# Zero_V1_0.net
KiCad netlist of a schematic drawn in EAGLE
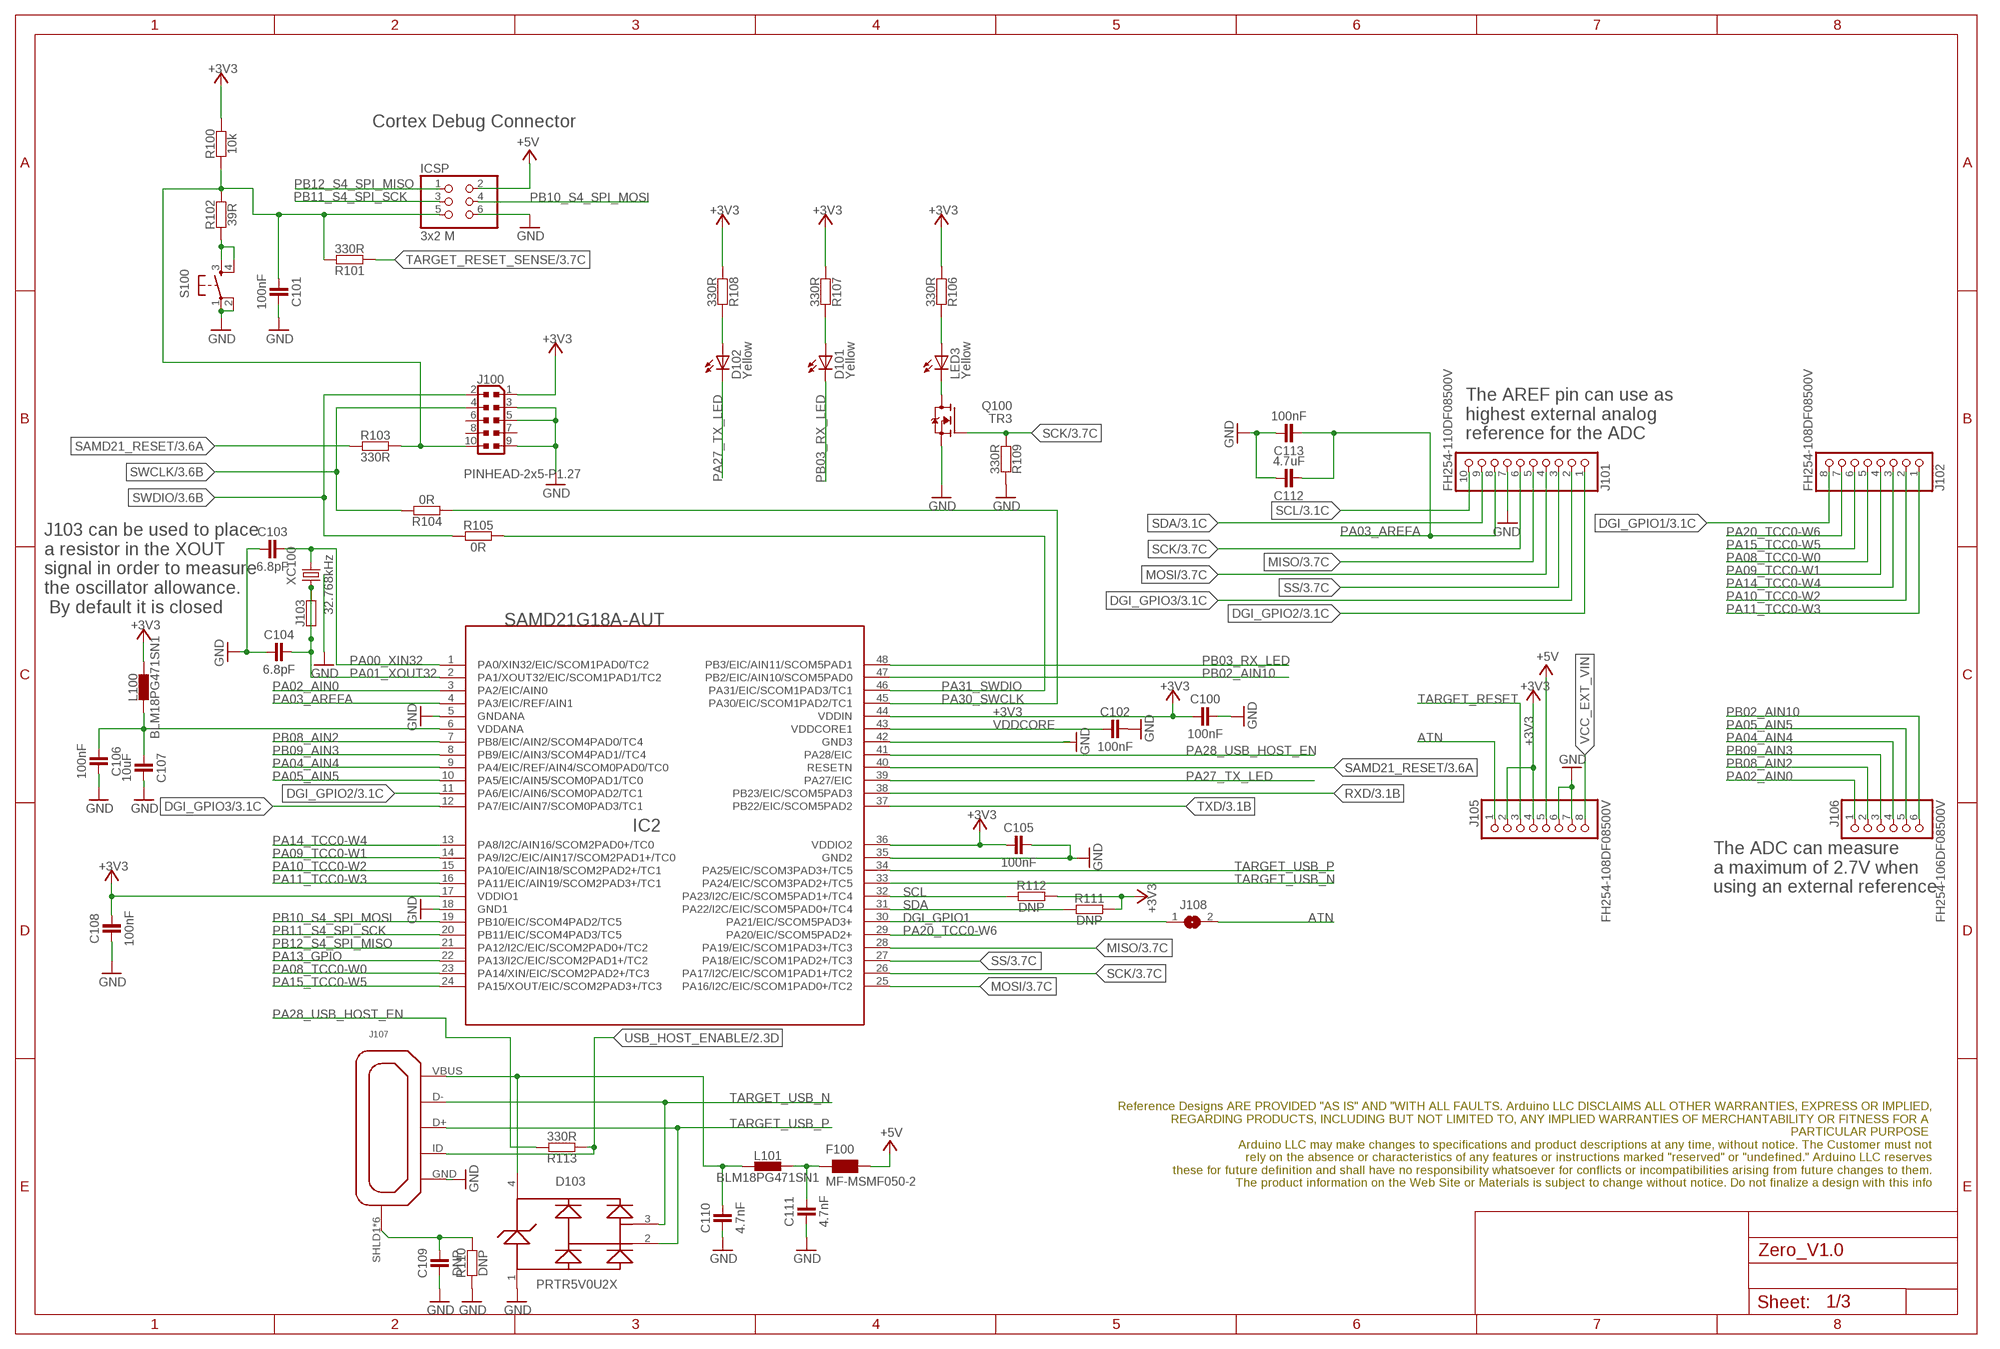
[diagram p0: schematic, sheet 1]
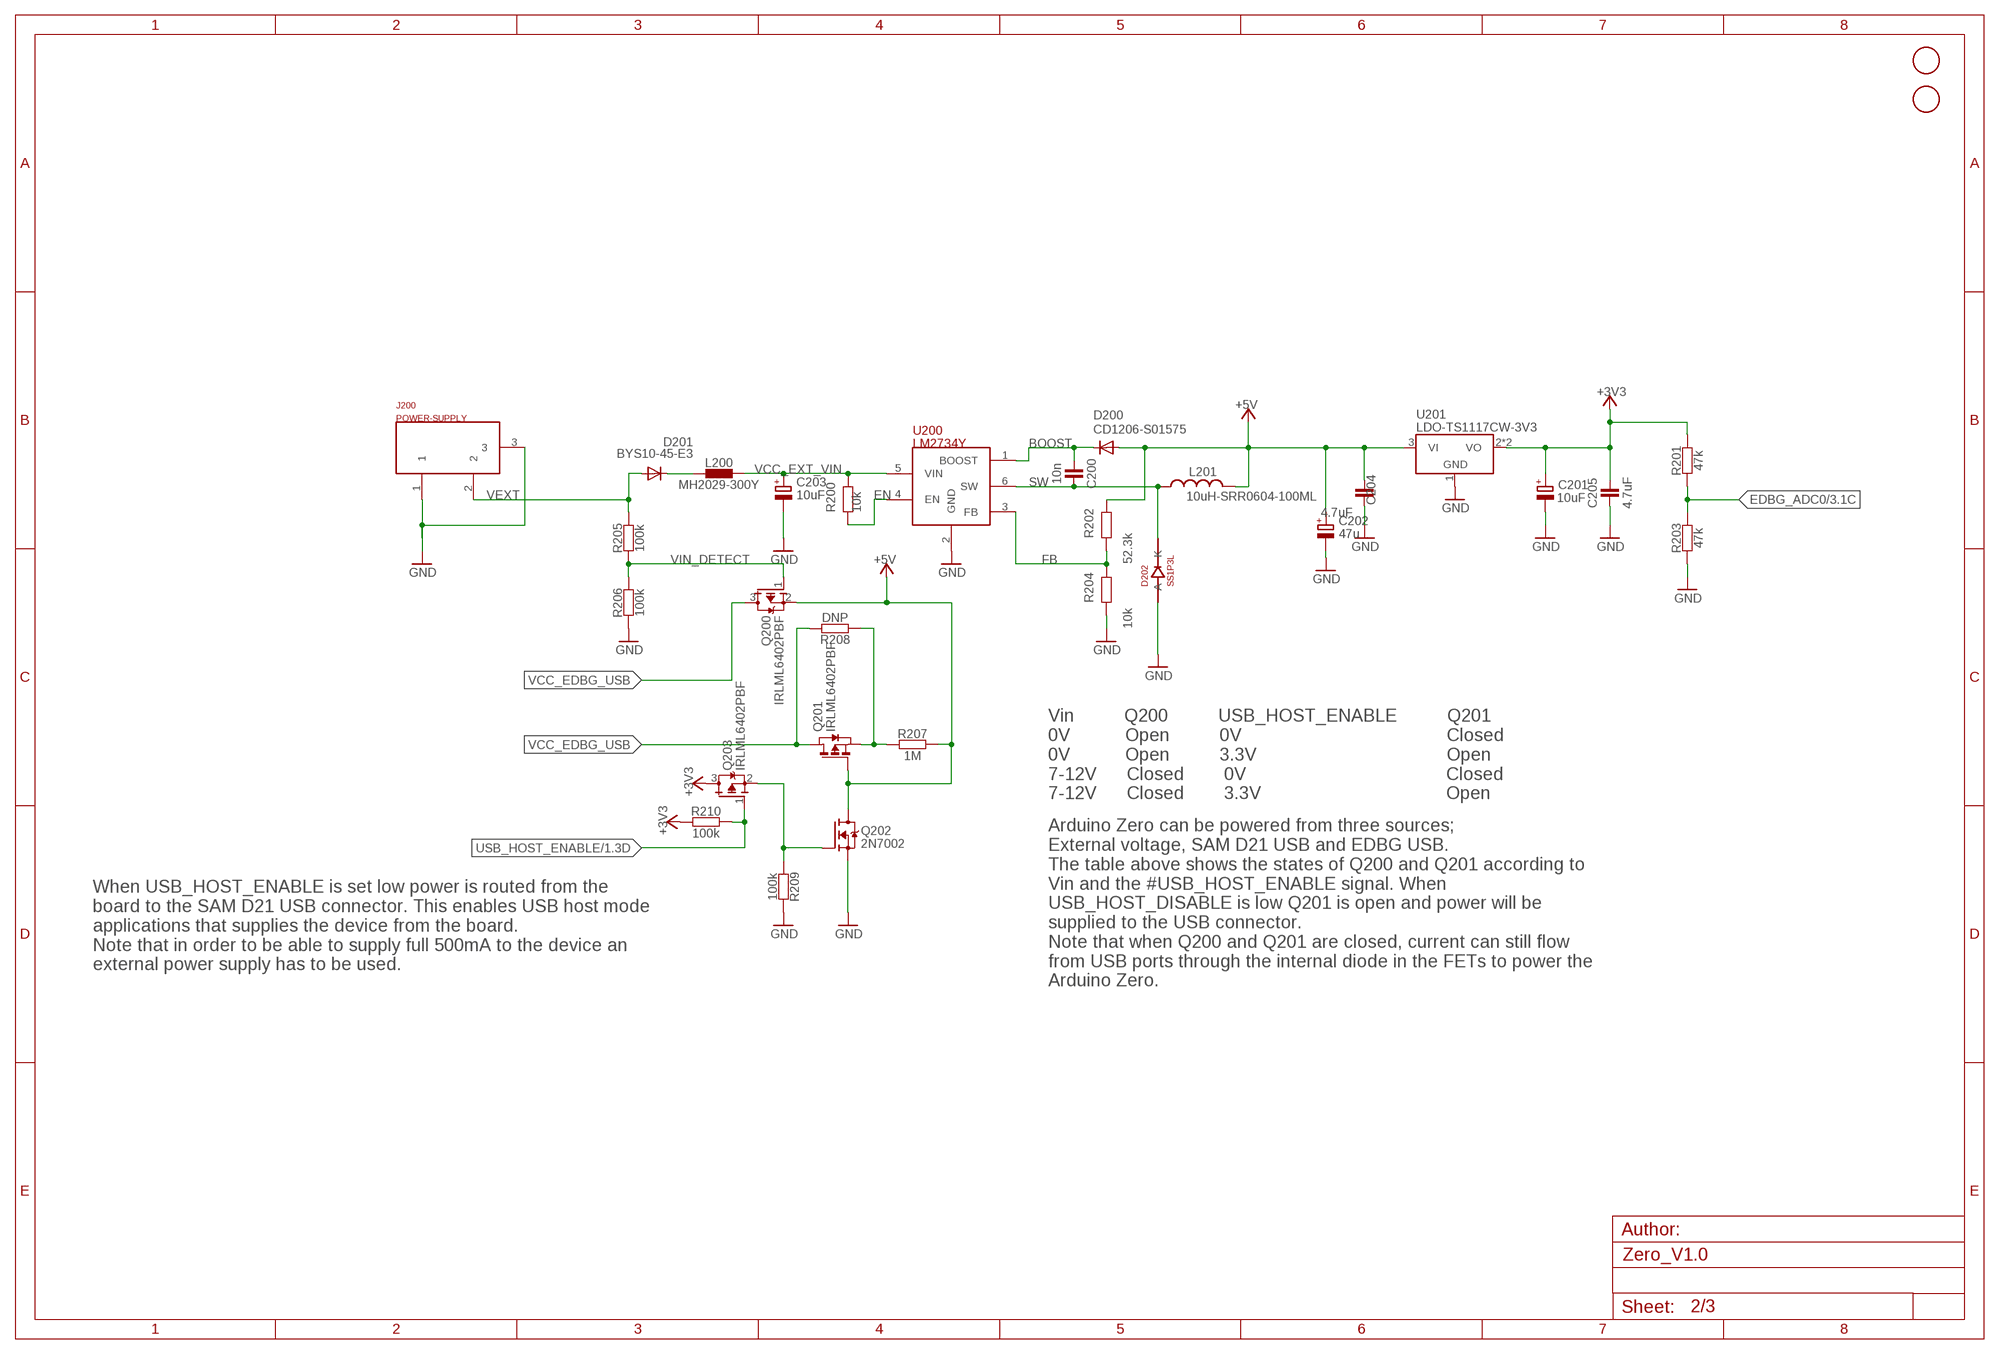
[diagram p1: schematic, sheet 2]
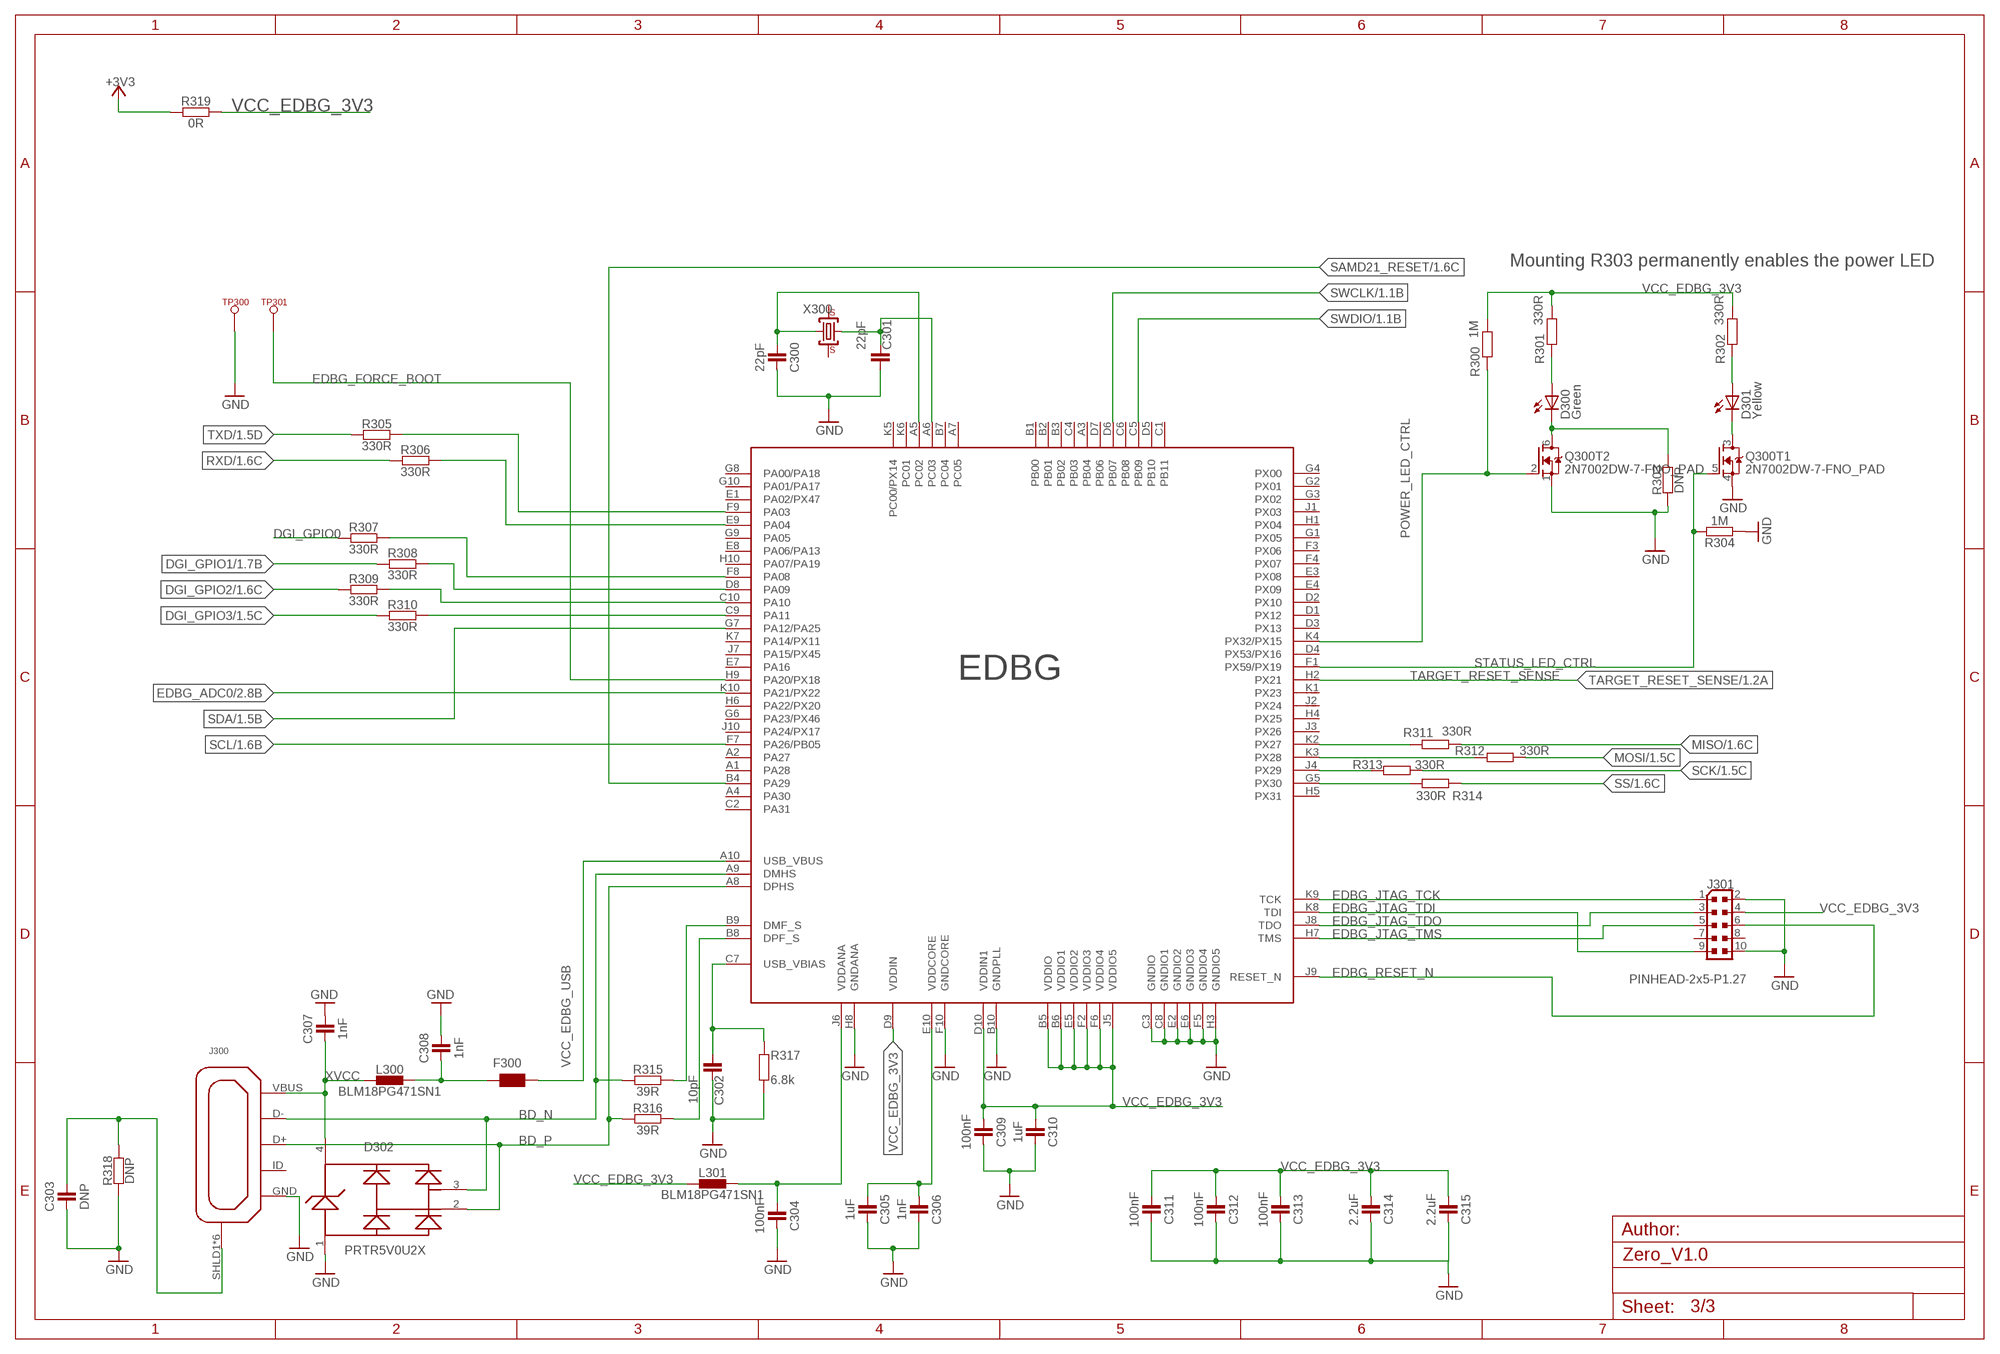
[diagram p2: schematic, sheet 3]

(export (version "E")
  (design (tool "Eeschema 10.0.6"))
  (components
    (comp (ref "C200")
      (value "10n")
      (footprint "eagle-import:C0402")
      (libsource (lib "eagle-import") (part "CAPACITORS-0402"))
    )
    (comp (ref "C201")
      (value "10uF")
      (footprint "eagle-import:PANASONIC_D")
      (fields (field (name "PART_NUMBER") "47uF"))
      (libsource (lib "eagle-import") (part "0113_47UF"))
    )
    (comp (ref "C202")
      (value "47u")
      (footprint "eagle-import:PANASONIC_D")
      (fields (field (name "PART_NUMBER") "47uF"))
      (libsource (lib "eagle-import") (part "0113_47UF"))
    )
    (comp (ref "C203")
      (value "10uF")
      (footprint "eagle-import:PANASONIC_D")
      (fields (field (name "PART_NUMBER") "47uF"))
      (libsource (lib "eagle-import") (part "0113_47UF"))
    )
    (comp (ref "C204")
      (value "4.7uF")
      (footprint "eagle-import:C0603")
      (libsource (lib "eagle-import") (part "CAPACITORS-0603"))
    )
    (comp (ref "C205")
      (value "4.7uF")
      (footprint "eagle-import:C0603")
      (libsource (lib "eagle-import") (part "CAPACITORS-0603"))
    )
    (comp (ref "D200")
      (value "CD1206-S01575")
      (footprint "eagle-import:MINIMELF")
      (libsource (lib "eagle-import") (part "0012_CD1206-S01575"))
    )
    (comp (ref "D201")
      (value "BYS10-45-E3")
      (footprint "eagle-import:MINIMELF")
      (fields (field (name "PART_NUMBER") "CD1206-S01575"))
      (libsource (lib "eagle-import") (part "0012_CD1206-S01575"))
    )
    (comp (ref "D202")
      (value "SS1P3L")
      (footprint "eagle-import:DO220AAL")
      (fields (field (name "PART_NUMBER") "SS1P3L-M3/84A"))
      (libsource (lib "eagle-import") (part "0025_SS1P3L-M3/84A"))
    )
    (comp (ref "FD1")
      (value "FIDUCIALMOUNT")
      (footprint "eagle-import:FIDUCIA-MOUNT")
      (libsource (lib "eagle-import") (part "FIDUCIALMOUNT"))
    )
    (comp (ref "FD2")
      (value "FIDUCIALMOUNT")
      (footprint "eagle-import:FIDUCIA-MOUNT")
      (libsource (lib "eagle-import") (part "FIDUCIALMOUNT"))
    )
    (comp (ref "J200")
      (value "POWER-SUPPLY")
      (footprint "eagle-import:POWERSUPPLY_DC-21MM")
      (fields (field (name "PART_NUMBER") "19746"))
      (libsource (lib "eagle-import") (part "0018_19746-POWER-SUPPLY"))
    )
    (comp (ref "L200")
      (value "MH2029-300Y")
      (footprint "eagle-import:C0805")
      (libsource (lib "eagle-import") (part "INDUCTOR-0805"))
    )
    (comp (ref "L201")
      (value "10uH-SRR0604-100ML")
      (footprint "eagle-import:SRR0604")
      (fields (field (name "PART_NUMBER") "SRR0604-100ML"))
      (libsource (lib "eagle-import") (part "0031_SRR0604-100ML"))
    )
    (comp (ref "Q200")
      (value "IRLML6402PBF")
      (footprint "eagle-import:SOT323")
      (libsource (lib "eagle-import") (part "IRLML6402PBF"))
    )
    (comp (ref "Q201")
      (value "IRLML6402PBF")
      (footprint "eagle-import:SOT-23")
      (fields (field (name "PART_NUMBER") "PMV48XP"))
      (libsource (lib "eagle-import") (part "0297_PMV48XP"))
    )
    (comp (ref "Q202")
      (value "2N7002")
      (footprint "eagle-import:SOT23")
      (libsource (lib "eagle-import") (part "MOSFET-N-SOT23"))
    )
    (comp (ref "Q203")
      (value "IRLML6402PBF")
      (footprint "eagle-import:SOT323")
      (libsource (lib "eagle-import") (part "IRLML6402PBF"))
    )
    (comp (ref "R200")
      (value "10k")
      (footprint "eagle-import:C0402")
      (libsource (lib "eagle-import") (part "RESISTORS-0402"))
    )
    (comp (ref "R201")
      (value "47k")
      (footprint "eagle-import:C0402")
      (libsource (lib "eagle-import") (part "RESISTORS-0402"))
    )
    (comp (ref "R202")
      (value "52.3k")
      (footprint "eagle-import:C0402")
      (libsource (lib "eagle-import") (part "RESISTORS-0402"))
    )
    (comp (ref "R203")
      (value "47k")
      (footprint "eagle-import:C0402")
      (libsource (lib "eagle-import") (part "RESISTORS-0402"))
    )
    (comp (ref "R204")
      (value "10k")
      (footprint "eagle-import:C0402")
      (libsource (lib "eagle-import") (part "RESISTORS-0402"))
    )
    (comp (ref "R205")
      (value "100k")
      (footprint "eagle-import:C0402")
      (libsource (lib "eagle-import") (part "RESISTORS-0402"))
    )
    (comp (ref "R206")
      (value "100k")
      (footprint "eagle-import:C0402")
      (libsource (lib "eagle-import") (part "RESISTORS-0402"))
    )
    (comp (ref "R207")
      (value "1M")
      (footprint "eagle-import:C0402")
      (libsource (lib "eagle-import") (part "RESISTORS-0402"))
    )
    (comp (ref "R208")
      (value "DNP")
      (footprint "eagle-import:C0402")
      (libsource (lib "eagle-import") (part "RESISTORS-0402"))
    )
    (comp (ref "R209")
      (value "100k")
      (footprint "eagle-import:C0402")
      (libsource (lib "eagle-import") (part "RESISTORS-0402"))
    )
    (comp (ref "R210")
      (value "100k")
      (footprint "eagle-import:C0402")
      (libsource (lib "eagle-import") (part "RESISTORS-0402"))
    )
    (comp (ref "U200")
      (value "LM2734Y")
      (footprint "eagle-import:SOT23-6")
      (fields (field (name "PART_NUMBER") "LM2734YMK"))
      (libsource (lib "eagle-import") (part "0179_LM2734YMK"))
    )
    (comp (ref "U201")
      (value "LDO-TS1117CW-3V3")
      (footprint "eagle-import:SOT223")
      (libsource (lib "eagle-import") (part "LDO-TS1117CW-3V3"))
    )
    (comp (ref "C300")
      (value "22pF")
      (footprint "eagle-import:C0402")
      (libsource (lib "eagle-import") (part "CAPACITORS-0402"))
    )
    (comp (ref "C301")
      (value "22pF")
      (footprint "eagle-import:C0402")
      (libsource (lib "eagle-import") (part "CAPACITORS-0402"))
    )
    (comp (ref "C302")
      (value "10pF")
      (footprint "eagle-import:C0402")
      (libsource (lib "eagle-import") (part "CAPACITORS-0402"))
    )
    (comp (ref "C303")
      (value "DNP")
      (footprint "eagle-import:C0402")
      (libsource (lib "eagle-import") (part "CAPACITORS-0402"))
    )
    (comp (ref "C304")
      (value "100nF")
      (footprint "eagle-import:C0402")
      (libsource (lib "eagle-import") (part "CAPACITORS-0402"))
    )
    (comp (ref "C305")
      (value "1uF")
      (footprint "eagle-import:C0402")
      (libsource (lib "eagle-import") (part "CAPACITORS-0402"))
    )
    (comp (ref "C306")
      (value "1nF")
      (footprint "eagle-import:C0402")
      (libsource (lib "eagle-import") (part "CAPACITORS-0402"))
    )
    (comp (ref "C307")
      (value "1nF")
      (footprint "eagle-import:C0402")
      (libsource (lib "eagle-import") (part "CAPACITORS-0402"))
    )
    (comp (ref "C308")
      (value "1nF")
      (footprint "eagle-import:C0402")
      (libsource (lib "eagle-import") (part "CAPACITORS-0402"))
    )
    (comp (ref "C309")
      (value "100nF")
      (footprint "eagle-import:C0402")
      (libsource (lib "eagle-import") (part "CAPACITORS-0402"))
    )
    (comp (ref "C310")
      (value "1uF")
      (footprint "eagle-import:C0402")
      (libsource (lib "eagle-import") (part "CAPACITORS-0402"))
    )
    (comp (ref "C311")
      (value "100nF")
      (footprint "eagle-import:C0402")
      (libsource (lib "eagle-import") (part "CAPACITORS-0402"))
    )
    (comp (ref "C312")
      (value "100nF")
      (footprint "eagle-import:C0402")
      (libsource (lib "eagle-import") (part "CAPACITORS-0402"))
    )
    (comp (ref "C313")
      (value "100nF")
      (footprint "eagle-import:C0402")
      (libsource (lib "eagle-import") (part "CAPACITORS-0402"))
    )
    (comp (ref "C314")
      (value "2.2uF")
      (footprint "eagle-import:C0402")
      (libsource (lib "eagle-import") (part "CAPACITORS-0402"))
    )
    (comp (ref "C315")
      (value "2.2uF")
      (footprint "eagle-import:C0402")
      (libsource (lib "eagle-import") (part "CAPACITORS-0402"))
    )
    (comp (ref "D300")
      (value "Green")
      (footprint "eagle-import:CHIPLED_0805")
      (fields (field (name "PART_NUMBER") "KPT-2012SGC"))
      (libsource (lib "eagle-import") (part "0043_KPT-2012SGC"))
    )
    (comp (ref "D301")
      (value "Yellow")
      (footprint "eagle-import:CHIPLED_0805")
      (fields (field (name "PART_NUMBER") "KPT-2012SGC"))
      (libsource (lib "eagle-import") (part "0043_KPT-2012SGC"))
    )
    (comp (ref "D302")
      (value "PRTR5V0U2XB")
      (footprint "eagle-import:SOT143B")
      (libsource (lib "eagle-import") (part "PRTR5V0U2XB"))
    )
    (comp (ref "EDBG")
      (value "EDBG")
      (footprint "eagle-import:VFBGA100")
      (libsource (lib "eagle-import") (part "EDBG"))
    )
    (comp (ref "F300")
      (value "WUERTH-ELEKTRONIK_WE-CBF_1812")
      (footprint "eagle-import:WUERTH-ELEKTRONIK_1812")
      (libsource (lib "eagle-import") (part "WUERTH-ELEKTRONIK_WE-CBF_1812"))
    )
    (comp (ref "J300")
      (value "ZX62-AB-5PA")
      (footprint "eagle-import:USB-MICRO-10103594")
      (libsource (lib "eagle-import") (part "ZX62-AB-5PA"))
    )
    (comp (ref "J301")
      (value "PINHEAD-2x5-P1.27")
      (footprint "eagle-import:PINHEAD_2X05_127")
      (libsource (lib "eagle-import") (part "0171_PH127-205DF055G00AROUND-PADS"))
    )
    (comp (ref "L300")
      (value "BLM18PG471SN1")
      (footprint "eagle-import:C0603")
      (libsource (lib "eagle-import") (part "INDUCTOR-0603"))
    )
    (comp (ref "L301")
      (value "BLM18PG471SN1")
      (footprint "eagle-import:C0603")
      (libsource (lib "eagle-import") (part "INDUCTOR-0603"))
    )
    (comp (ref "Q300")
      (value "2N7002DW-7-FNO_PAD")
      (footprint "eagle-import:PWR_SC70-6L2")
      (libsource (lib "eagle-import") (part "2N7002DW-7-FNO_PAD"))
    )
    (comp (ref "R300")
      (value "1M")
      (footprint "eagle-import:C0402")
      (libsource (lib "eagle-import") (part "RESISTORS-0402"))
    )
    (comp (ref "R301")
      (value "330R")
      (footprint "eagle-import:C0402")
      (libsource (lib "eagle-import") (part "RESISTORS-0402"))
    )
    (comp (ref "R302")
      (value "330R")
      (footprint "eagle-import:C0402")
      (libsource (lib "eagle-import") (part "RESISTORS-0402"))
    )
    (comp (ref "R303")
      (value "DNP")
      (footprint "eagle-import:C0402")
      (libsource (lib "eagle-import") (part "RESISTORS-0402"))
    )
    (comp (ref "R304")
      (value "1M")
      (footprint "eagle-import:C0402")
      (libsource (lib "eagle-import") (part "RESISTORS-0402"))
    )
    (comp (ref "R305")
      (value "330R")
      (footprint "eagle-import:C0402")
      (libsource (lib "eagle-import") (part "RESISTORS-0402"))
    )
    (comp (ref "R306")
      (value "330R")
      (footprint "eagle-import:C0402")
      (libsource (lib "eagle-import") (part "RESISTORS-0402"))
    )
    (comp (ref "R307")
      (value "330R")
      (footprint "eagle-import:C0402")
      (libsource (lib "eagle-import") (part "RESISTORS-0402"))
    )
    (comp (ref "R308")
      (value "330R")
      (footprint "eagle-import:C0402")
      (libsource (lib "eagle-import") (part "RESISTORS-0402"))
    )
    (comp (ref "R309")
      (value "330R")
      (footprint "eagle-import:C0402")
      (libsource (lib "eagle-import") (part "RESISTORS-0402"))
    )
    (comp (ref "R310")
      (value "330R")
      (footprint "eagle-import:C0402")
      (libsource (lib "eagle-import") (part "RESISTORS-0402"))
    )
    (comp (ref "R311")
      (value "330R")
      (footprint "eagle-import:C0402")
      (libsource (lib "eagle-import") (part "RESISTORS-0402"))
    )
    (comp (ref "R312")
      (value "330R")
      (footprint "eagle-import:C0402")
      (libsource (lib "eagle-import") (part "RESISTORS-0402"))
    )
    (comp (ref "R313")
      (value "330R")
      (footprint "eagle-import:C0402")
      (libsource (lib "eagle-import") (part "RESISTORS-0402"))
    )
    (comp (ref "R314")
      (value "330R")
      (footprint "eagle-import:C0402")
      (libsource (lib "eagle-import") (part "RESISTORS-0402"))
    )
    (comp (ref "R315")
      (value "39R")
      (footprint "eagle-import:C0402")
      (libsource (lib "eagle-import") (part "RESISTORS-0402"))
    )
    (comp (ref "R316")
      (value "39R")
      (footprint "eagle-import:C0402")
      (libsource (lib "eagle-import") (part "RESISTORS-0402"))
    )
    (comp (ref "R317")
      (value "6.8k")
      (footprint "eagle-import:C0402")
      (libsource (lib "eagle-import") (part "RESISTORS-0402"))
    )
    (comp (ref "R318")
      (value "DNP")
      (footprint "eagle-import:C0402")
      (libsource (lib "eagle-import") (part "RESISTORS-0402"))
    )
    (comp (ref "R319")
      (value "0R")
      (footprint "eagle-import:C0402")
      (libsource (lib "eagle-import") (part "RESISTORS-0402"))
    )
    (comp (ref "TP300")
      (value "TP_SP")
      (footprint "eagle-import:TP-SP")
      (libsource (lib "eagle-import") (part "TP_SP"))
    )
    (comp (ref "TP301")
      (value "TP_SP")
      (footprint "eagle-import:TP-SP")
      (libsource (lib "eagle-import") (part "TP_SP"))
    )
    (comp (ref "X300")
      (value "12mHz-12pF-K7")
      (footprint "eagle-import:CRYSTAL-5.4-3.2")
      (libsource (lib "eagle-import") (part "12MHZ-12PF-K75.4-3.2"))
    )
    (comp (ref "C100")
      (value "100nF")
      (footprint "eagle-import:C0402")
      (libsource (lib "eagle-import") (part "CAPACITORS-0402"))
    )
    (comp (ref "C101")
      (value "100nF")
      (footprint "eagle-import:C0402")
      (libsource (lib "eagle-import") (part "CAPACITORS-0402"))
    )
    (comp (ref "C102")
      (value "100nF")
      (footprint "eagle-import:C0402")
      (libsource (lib "eagle-import") (part "CAPACITORS-0402"))
    )
    (comp (ref "C103")
      (value "6.8pF")
      (footprint "eagle-import:C0402")
      (libsource (lib "eagle-import") (part "CAPACITORS-0402"))
    )
    (comp (ref "C104")
      (value "6.8pF")
      (footprint "eagle-import:C0402")
      (libsource (lib "eagle-import") (part "CAPACITORS-0402"))
    )
    (comp (ref "C105")
      (value "100nF")
      (footprint "eagle-import:C0402")
      (libsource (lib "eagle-import") (part "CAPACITORS-0402"))
    )
    (comp (ref "C106")
      (value "100nF")
      (footprint "eagle-import:C0402")
      (libsource (lib "eagle-import") (part "CAPACITORS-0402"))
    )
    (comp (ref "C107")
      (value "10uF")
      (footprint "eagle-import:C0603")
      (libsource (lib "eagle-import") (part "CAPACITORS-0603"))
    )
    (comp (ref "C108")
      (value "100nF")
      (footprint "eagle-import:C0402")
      (libsource (lib "eagle-import") (part "CAPACITORS-0402"))
    )
    (comp (ref "C109")
      (value "DNP")
      (footprint "eagle-import:C0402")
      (libsource (lib "eagle-import") (part "CAPACITORS-0402"))
    )
    (comp (ref "C110")
      (value "4.7nF")
      (footprint "eagle-import:C0402")
      (libsource (lib "eagle-import") (part "CAPACITORS-0402"))
    )
    (comp (ref "C111")
      (value "4.7nF")
      (footprint "eagle-import:C0402")
      (libsource (lib "eagle-import") (part "CAPACITORS-0402"))
    )
    (comp (ref "C112")
      (value "4.7uF")
      (footprint "eagle-import:C0603")
      (libsource (lib "eagle-import") (part "CAPACITORS-0603"))
    )
    (comp (ref "C113")
      (value "100nF")
      (footprint "eagle-import:C0402")
      (libsource (lib "eagle-import") (part "CAPACITORS-0402"))
    )
    (comp (ref "D101")
      (value "Yellow")
      (footprint "eagle-import:CHIPLED_0805")
      (fields (field (name "PART_NUMBER") "KPT-2012YC"))
      (libsource (lib "eagle-import") (part "0044_KPT-2012YC"))
    )
    (comp (ref "D102")
      (value "Yellow")
      (footprint "eagle-import:CHIPLED_0805")
      (fields (field (name "PART_NUMBER") "KPT-2012YC"))
      (libsource (lib "eagle-import") (part "0044_KPT-2012YC"))
    )
    (comp (ref "D103")
      (value "PRTR5V0U2XB")
      (footprint "eagle-import:SOT143B")
      (libsource (lib "eagle-import") (part "PRTR5V0U2XB"))
    )
    (comp (ref "F100")
      (value "MF-MSMF050-2")
      (footprint "eagle-import:WUERTH-ELEKTRONIK_1812")
      (libsource (lib "eagle-import") (part "WUERTH-ELEKTRONIK_WE-CBF_1812"))
    )
    (comp (ref "IC2")
      (value "SAMD21G18A-AUT")
      (footprint "eagle-import:TQFP48")
      (libsource (lib "eagle-import") (part "SAMD21G18A"))
    )
    (comp (ref "ICSP")
      (value "3x2 M")
      (footprint "eagle-import:2X03")
      (libsource (lib "eagle-import") (part "ICSP"))
    )
    (comp (ref "J100")
      (value "PINHEAD-2x5-P1.27")
      (footprint "eagle-import:PINHEAD_2X05_127")
      (libsource (lib "eagle-import") (part "0171_PH127-205DF055G00AROUND-PADS"))
    )
    (comp (ref "J101")
      (value "FH254-110DF08500V")
      (footprint "eagle-import:1X10")
      (fields (field (name "PART_NUMBER") "20TW-537"))
      (libsource (lib "eagle-import") (part "1684_20TW-537"))
    )
    (comp (ref "J102")
      (value "FH254-108DF08500V")
      (footprint "eagle-import:1X08")
      (fields (field (name "PART_NUMBER") "20TW-536"))
      (libsource (lib "eagle-import") (part "1683_20TW-536"))
    )
    (comp (ref "J103")
      (value "RESISTORS-0402")
      (footprint "eagle-import:C0402")
      (libsource (lib "eagle-import") (part "RESISTORS-0402"))
    )
    (comp (ref "J105")
      (value "FH254-108DF08500V")
      (footprint "eagle-import:1X08")
      (fields (field (name "PART_NUMBER") "20TW-536"))
      (libsource (lib "eagle-import") (part "1683_20TW-536"))
    )
    (comp (ref "J106")
      (value "FH254-106DF08500V")
      (footprint "eagle-import:1X06")
      (fields (field (name "PART_NUMBER") "20TW-535"))
      (libsource (lib "eagle-import") (part "1682_20TW-535_STD"))
    )
    (comp (ref "J107")
      (value "ZX62-AB-5PA")
      (footprint "eagle-import:USB-MICRO-10103594")
      (libsource (lib "eagle-import") (part "ZX62-AB-5PA"))
    )
    (comp (ref "J108")
      (value "SJ")
      (footprint "eagle-import:SJ")
      (libsource (lib "eagle-import") (part "SJ"))
    )
    (comp (ref "L100")
      (value "BLM18PG471SN1")
      (footprint "eagle-import:C0603")
      (libsource (lib "eagle-import") (part "INDUCTOR-0603"))
    )
    (comp (ref "L101")
      (value "BLM18PG471SN1")
      (footprint "eagle-import:C0603")
      (libsource (lib "eagle-import") (part "INDUCTOR-0603"))
    )
    (comp (ref "LED3")
      (value "Yellow")
      (footprint "eagle-import:CHIPLED_0805")
      (fields (field (name "PART_NUMBER") "KPT-2012YC"))
      (libsource (lib "eagle-import") (part "0044_KPT-2012YC"))
    )
    (comp (ref "R100")
      (value "10k")
      (footprint "eagle-import:C0402")
      (libsource (lib "eagle-import") (part "RESISTORS-0402"))
    )
    (comp (ref "R101")
      (value "330R")
      (footprint "eagle-import:C0402")
      (libsource (lib "eagle-import") (part "RESISTORS-0402"))
    )
    (comp (ref "R102")
      (value "39R")
      (footprint "eagle-import:C0402")
      (libsource (lib "eagle-import") (part "RESISTORS-0402"))
    )
    (comp (ref "R103")
      (value "330R")
      (footprint "eagle-import:C0402")
      (libsource (lib "eagle-import") (part "RESISTORS-0402"))
    )
    (comp (ref "R104")
      (value "0R")
      (footprint "eagle-import:C0402")
      (libsource (lib "eagle-import") (part "RESISTORS-0402"))
    )
    (comp (ref "R105")
      (value "0R")
      (footprint "eagle-import:C0402")
      (libsource (lib "eagle-import") (part "RESISTORS-0402"))
    )
    (comp (ref "R106")
      (value "330R")
      (footprint "eagle-import:C0402")
      (libsource (lib "eagle-import") (part "RESISTORS-0402"))
    )
    (comp (ref "R107")
      (value "330R")
      (footprint "eagle-import:C0402")
      (libsource (lib "eagle-import") (part "RESISTORS-0402"))
    )
    (comp (ref "R108")
      (value "330R")
      (footprint "eagle-import:C0402")
      (libsource (lib "eagle-import") (part "RESISTORS-0402"))
    )
    (comp (ref "R109")
      (value "330R")
      (footprint "eagle-import:C0402")
      (libsource (lib "eagle-import") (part "RESISTORS-0402"))
    )
    (comp (ref "R110")
      (value "DNP")
      (footprint "eagle-import:C0402")
      (libsource (lib "eagle-import") (part "RESISTORS-0402"))
    )
    (comp (ref "R111")
      (value "DNP")
      (footprint "eagle-import:C0402")
      (libsource (lib "eagle-import") (part "RESISTORS-0402"))
    )
    (comp (ref "R112")
      (value "DNP")
      (footprint "eagle-import:C0402")
      (libsource (lib "eagle-import") (part "RESISTORS-0402"))
    )
    (comp (ref "R113")
      (value "330R")
      (footprint "eagle-import:C0402")
      (libsource (lib "eagle-import") (part "RESISTORS-0402"))
    )
    (comp (ref "S100")
      (value "PUSHBUTTON3")
      (footprint "eagle-import:TS42_4PINS")
      (libsource (lib "eagle-import") (part "PUSHBUTTON3"))
    )
    (comp (ref "TR3")
      (value "Q100")
      (footprint "eagle-import:SOT-23")
      (libsource (lib "eagle-import") (part "1612_2N7002LT1G"))
    )
    (comp (ref "U$5")
      (value "DNP")
      (footprint "eagle-import:FRAME")
      (libsource (lib "eagle-import") (part "A3-FRAME-STANDARD"))
    )
    (comp (ref "XC100")
      (value "32.768kHz")
      (footprint "eagle-import:CRYSTAL_TC26SMD")
      (libsource (lib "eagle-import") (part "CRYSTALSMD"))
    )
  )
  (nets
    (net (code "1") (name "+3V3") (class "Default")
      (node (ref "C100") (pin "1") (pinfunction "1_1") (pintype "passive"))
      (node (ref "C105") (pin "1") (pinfunction "1_1") (pintype "passive"))
      (node (ref "C108") (pin "2") (pinfunction "2_2") (pintype "passive"))
      (node (ref "C201") (pin "+") (pinfunction "+_+") (pintype "passive"))
      (node (ref "C205") (pin "2") (pinfunction "2_2") (pintype "passive"))
      (node (ref "IC2") (pin "17") (pinfunction "VDDIO1_17") (pintype "power_in"))
      (node (ref "IC2") (pin "36") (pinfunction "VDDIO2_36") (pintype "power_in"))
      (node (ref "IC2") (pin "44") (pinfunction "VDDIN_44") (pintype "power_in"))
      (node (ref "J100") (pin "1") (pinfunction "1_1") (pintype "passive"))
      (node (ref "J105") (pin "2") (pinfunction "2_2") (pintype "passive"))
      (node (ref "J105") (pin "4") (pinfunction "4_4") (pintype "passive"))
      (node (ref "L100") (pin "2") (pinfunction "2_2") (pintype "passive"))
      (node (ref "Q203") (pin "3") (pinfunction "D_3") (pintype "passive"))
      (node (ref "R100") (pin "2") (pinfunction "2_2") (pintype "passive"))
      (node (ref "R106") (pin "1") (pinfunction "1_1") (pintype "passive"))
      (node (ref "R107") (pin "1") (pinfunction "1_1") (pintype "passive"))
      (node (ref "R108") (pin "1") (pinfunction "1_1") (pintype "passive"))
      (node (ref "R111") (pin "2") (pinfunction "2_2") (pintype "passive"))
      (node (ref "R112") (pin "2") (pinfunction "2_2") (pintype "passive"))
      (node (ref "R201") (pin "2") (pinfunction "2_2") (pintype "passive"))
      (node (ref "R210") (pin "1") (pinfunction "1_1") (pintype "passive"))
      (node (ref "R319") (pin "1") (pinfunction "1_1") (pintype "passive"))
      (node (ref "U201") (pin "2") (pinfunction "VO_2") (pintype "passive"))
      (node (ref "U201") (pin "4") (pinfunction "VO_4") (pintype "passive"))
    )
    (net (code "2") (name "+5V") (class "Default")
      (node (ref "C202") (pin "+") (pinfunction "+_+") (pintype "passive"))
      (node (ref "C204") (pin "1") (pinfunction "1_1") (pintype "passive"))
      (node (ref "D200") (pin "A") (pinfunction "A_A") (pintype "passive"))
      (node (ref "F100") (pin "2") (pinfunction "2_2") (pintype "passive"))
      (node (ref "ICSP") (pin "2") (pinfunction "2_2") (pintype "passive"))
      (node (ref "J105") (pin "5") (pinfunction "5_5") (pintype "passive"))
      (node (ref "L201") (pin "P$2") (pinfunction "2_P$2") (pintype "passive"))
      (node (ref "Q200") (pin "2") (pinfunction "S_2") (pintype "passive"))
      (node (ref "Q201") (pin "3") (pinfunction "G_3") (pintype "passive"))
      (node (ref "Q202") (pin "3") (pinfunction "D_3") (pintype "passive"))
      (node (ref "R202") (pin "1") (pinfunction "1_1") (pintype "passive"))
      (node (ref "R207") (pin "2") (pinfunction "2_2") (pintype "passive"))
      (node (ref "U201") (pin "3") (pinfunction "VI_3") (pintype "input"))
    )
    (net (code "3") (name "ATN") (class "Default")
      (node (ref "J105") (pin "1") (pinfunction "1_1") (pintype "passive"))
      (node (ref "J108") (pin "2") (pinfunction "2_2") (pintype "passive"))
    )
    (net (code "4") (name "BD_N") (class "Default")
      (node (ref "D302") (pin "3") (pinfunction "3_3") (pintype "bidirectional"))
      (node (ref "EDBG") (pin "A9") (pinfunction "DMHS_A9") (pintype "bidirectional"))
      (node (ref "J300") (pin "D-") (pinfunction "D-_D-") (pintype "bidirectional"))
      (node (ref "R315") (pin "1") (pinfunction "1_1") (pintype "passive"))
    )
    (net (code "5") (name "BD_P") (class "Default")
      (node (ref "D302") (pin "2") (pinfunction "2_2") (pintype "bidirectional"))
      (node (ref "EDBG") (pin "A8") (pinfunction "DPHS_A8") (pintype "bidirectional"))
      (node (ref "J300") (pin "D+") (pinfunction "D+_D+") (pintype "bidirectional"))
      (node (ref "R316") (pin "1") (pinfunction "1_1") (pintype "passive"))
    )
    (net (code "6") (name "BOOST") (class "Default")
      (node (ref "C200") (pin "1") (pinfunction "1_1") (pintype "passive"))
      (node (ref "D200") (pin "C") (pinfunction "C_C") (pintype "passive"))
      (node (ref "U200") (pin "1") (pinfunction "BOOST_1") (pintype "input"))
    )
    (net (code "7") (name "DGI_GPIO0") (class "Default")
      (node (ref "R307") (pin "1") (pinfunction "1_1") (pintype "passive"))
    )
    (net (code "8") (name "DGI_GPIO1") (class "Default")
      (node (ref "IC2") (pin "30") (pinfunction "PA21/EIC/SCOM5PAD3+_30") (pintype "bidirectional"))
      (node (ref "J102") (pin "8") (pinfunction "8_8") (pintype "passive"))
      (node (ref "J108") (pin "1") (pinfunction "1_1") (pintype "passive"))
      (node (ref "R308") (pin "1") (pinfunction "1_1") (pintype "passive"))
    )
    (net (code "9") (name "DGI_GPIO2") (class "Default")
      (node (ref "IC2") (pin "11") (pinfunction "PA6/EIC/AIN6/SCOM0PAD2/TC1_11") (pintype "bidirectional"))
      (node (ref "J101") (pin "1") (pinfunction "1_1") (pintype "passive"))
      (node (ref "R309") (pin "1") (pinfunction "1_1") (pintype "passive"))
    )
    (net (code "10") (name "DGI_GPIO3") (class "Default")
      (node (ref "IC2") (pin "12") (pinfunction "PA7/EIC/AIN7/SCOM0PAD3/TC1_12") (pintype "bidirectional"))
      (node (ref "J101") (pin "2") (pinfunction "2_2") (pintype "passive"))
      (node (ref "R310") (pin "1") (pinfunction "1_1") (pintype "passive"))
    )
    (net (code "11") (name "EDBG_ADC0") (class "Default")
      (node (ref "EDBG") (pin "K10") (pinfunction "PA21/PX22_K10") (pintype "bidirectional"))
      (node (ref "R201") (pin "1") (pinfunction "1_1") (pintype "passive"))
      (node (ref "R203") (pin "2") (pinfunction "2_2") (pintype "passive"))
    )
    (net (code "12") (name "EDBG_FORCE_BOOT") (class "Default")
      (node (ref "EDBG") (pin "H9") (pinfunction "PA20/PX18_H9") (pintype "bidirectional"))
      (node (ref "TP301") (pin "X") (pinfunction "TESTP_X") (pintype "passive"))
    )
    (net (code "13") (name "EDBG_JTAG_TCK") (class "Default")
      (node (ref "EDBG") (pin "K9") (pinfunction "TCK_K9") (pintype "bidirectional"))
      (node (ref "J301") (pin "1") (pinfunction "1_1") (pintype "passive"))
    )
    (net (code "14") (name "EDBG_JTAG_TDI") (class "Default")
      (node (ref "EDBG") (pin "K8") (pinfunction "TDI_K8") (pintype "bidirectional"))
      (node (ref "J301") (pin "9") (pinfunction "9_9") (pintype "passive"))
    )
    (net (code "15") (name "EDBG_JTAG_TDO") (class "Default")
      (node (ref "EDBG") (pin "J8") (pinfunction "TDO_J8") (pintype "bidirectional"))
      (node (ref "J301") (pin "3") (pinfunction "3_3") (pintype "passive"))
    )
    (net (code "16") (name "EDBG_JTAG_TMS") (class "Default")
      (node (ref "EDBG") (pin "H7") (pinfunction "TMS_H7") (pintype "bidirectional"))
      (node (ref "J301") (pin "5") (pinfunction "5_5") (pintype "passive"))
    )
    (net (code "17") (name "EDBG_RESET_N") (class "Default")
      (node (ref "EDBG") (pin "J9") (pinfunction "RESET_N_J9") (pintype "bidirectional"))
      (node (ref "J301") (pin "6") (pinfunction "6_6") (pintype "passive"))
    )
    (net (code "18") (name "EN") (class "Default")
      (node (ref "R200") (pin "2") (pinfunction "2_2") (pintype "passive"))
      (node (ref "U200") (pin "4") (pinfunction "EN_4") (pintype "input"))
    )
    (net (code "19") (name "FB") (class "Default")
      (node (ref "R202") (pin "2") (pinfunction "2_2") (pintype "passive"))
      (node (ref "R204") (pin "1") (pinfunction "1_1") (pintype "passive"))
      (node (ref "U200") (pin "3") (pinfunction "FB_3") (pintype "input"))
    )
    (net (code "20") (name "GND") (class "Default")
      (node (ref "C100") (pin "2") (pinfunction "2_2") (pintype "passive"))
      (node (ref "C101") (pin "2") (pinfunction "2_2") (pintype "passive"))
      (node (ref "C102") (pin "2") (pinfunction "2_2") (pintype "passive"))
      (node (ref "C103") (pin "1") (pinfunction "1_1") (pintype "passive"))
      (node (ref "C104") (pin "1") (pinfunction "1_1") (pintype "passive"))
      (node (ref "C105") (pin "2") (pinfunction "2_2") (pintype "passive"))
      (node (ref "C106") (pin "2") (pinfunction "2_2") (pintype "passive"))
      (node (ref "C107") (pin "2") (pinfunction "2_2") (pintype "passive"))
      (node (ref "C108") (pin "1") (pinfunction "1_1") (pintype "passive"))
      (node (ref "C109") (pin "1") (pinfunction "1_1") (pintype "passive"))
      (node (ref "C110") (pin "1") (pinfunction "1_1") (pintype "passive"))
      (node (ref "C111") (pin "1") (pinfunction "1_1") (pintype "passive"))
      (node (ref "C112") (pin "2") (pinfunction "2_2") (pintype "passive"))
      (node (ref "C113") (pin "2") (pinfunction "2_2") (pintype "passive"))
      (node (ref "C201") (pin "-") (pinfunction "-_-") (pintype "passive"))
      (node (ref "C202") (pin "-") (pinfunction "-_-") (pintype "passive"))
      (node (ref "C203") (pin "-") (pinfunction "-_-") (pintype "passive"))
      (node (ref "C204") (pin "2") (pinfunction "2_2") (pintype "passive"))
      (node (ref "C205") (pin "1") (pinfunction "1_1") (pintype "passive"))
      (node (ref "C300") (pin "2") (pinfunction "2_2") (pintype "passive"))
      (node (ref "C301") (pin "2") (pinfunction "2_2") (pintype "passive"))
      (node (ref "C302") (pin "2") (pinfunction "2_2") (pintype "passive"))
      (node (ref "C303") (pin "1") (pinfunction "1_1") (pintype "passive"))
      (node (ref "C304") (pin "2") (pinfunction "2_2") (pintype "passive"))
      (node (ref "C305") (pin "2") (pinfunction "2_2") (pintype "passive"))
      (node (ref "C306") (pin "2") (pinfunction "2_2") (pintype "passive"))
      (node (ref "C307") (pin "2") (pinfunction "2_2") (pintype "passive"))
      (node (ref "C308") (pin "2") (pinfunction "2_2") (pintype "passive"))
      (node (ref "C309") (pin "2") (pinfunction "2_2") (pintype "passive"))
      (node (ref "C310") (pin "2") (pinfunction "2_2") (pintype "passive"))
      (node (ref "C311") (pin "2") (pinfunction "2_2") (pintype "passive"))
      (node (ref "C312") (pin "2") (pinfunction "2_2") (pintype "passive"))
      (node (ref "C313") (pin "2") (pinfunction "2_2") (pintype "passive"))
      (node (ref "C314") (pin "2") (pinfunction "2_2") (pintype "passive"))
      (node (ref "C315") (pin "2") (pinfunction "2_2") (pintype "passive"))
      (node (ref "D103") (pin "1") (pinfunction "1_1") (pintype "bidirectional"))
      (node (ref "D202") (pin "P$2") (pinfunction "A_P$2") (pintype "bidirectional"))
      (node (ref "D302") (pin "1") (pinfunction "1_1") (pintype "bidirectional"))
      (node (ref "EDBG") (pin "B10") (pinfunction "GNDPLL_B10") (pintype "bidirectional"))
      (node (ref "EDBG") (pin "C3") (pinfunction "GNDIO_C3") (pintype "bidirectional"))
      (node (ref "EDBG") (pin "C8") (pinfunction "GNDIO1_C8") (pintype "bidirectional"))
      (node (ref "EDBG") (pin "E2") (pinfunction "GNDIO2_E2") (pintype "bidirectional"))
      (node (ref "EDBG") (pin "E6") (pinfunction "GNDIO3_E6") (pintype "bidirectional"))
      (node (ref "EDBG") (pin "F10") (pinfunction "GNDCORE_F10") (pintype "bidirectional"))
      (node (ref "EDBG") (pin "F5") (pinfunction "GNDIO4_F5") (pintype "bidirectional"))
      (node (ref "EDBG") (pin "H3") (pinfunction "GNDIO5_H3") (pintype "bidirectional"))
      (node (ref "EDBG") (pin "H8") (pinfunction "GNDANA_H8") (pintype "bidirectional"))
      (node (ref "IC2") (pin "18") (pinfunction "GND1_18") (pintype "power_in"))
      (node (ref "IC2") (pin "35") (pinfunction "GND2_35") (pintype "power_in"))
      (node (ref "IC2") (pin "42") (pinfunction "GND3_42") (pintype "power_in"))
      (node (ref "IC2") (pin "5") (pinfunction "GNDANA_5") (pintype "power_in"))
      (node (ref "ICSP") (pin "6") (pinfunction "6_6") (pintype "passive"))
      (node (ref "J100") (pin "3") (pinfunction "3_3") (pintype "passive"))
      (node (ref "J100") (pin "5") (pinfunction "5_5") (pintype "passive"))
      (node (ref "J100") (pin "9") (pinfunction "9_9") (pintype "passive"))
      (node (ref "J101") (pin "7") (pinfunction "7_7") (pintype "passive"))
      (node (ref "J105") (pin "6") (pinfunction "6_6") (pintype "passive"))
      (node (ref "J105") (pin "7") (pinfunction "7_7") (pintype "passive"))
      (node (ref "J107") (pin "GND") (pinfunction "GND_GND") (pintype "bidirectional"))
      (node (ref "J200") (pin "1") (pinfunction "1_1") (pintype "power_in"))
      (node (ref "J200") (pin "3") (pinfunction "3_3") (pintype "power_in"))
      (node (ref "J300") (pin "GND") (pinfunction "GND_GND") (pintype "bidirectional"))
      (node (ref "J301") (pin "10") (pinfunction "10_10") (pintype "passive"))
      (node (ref "J301") (pin "2") (pinfunction "2_2") (pintype "passive"))
      (node (ref "Q202") (pin "2") (pinfunction "S_2") (pintype "passive"))
      (node (ref "Q300") (pin "1") (pinfunction "S_1") (pintype "passive"))
      (node (ref "Q300") (pin "4") (pinfunction "S_4") (pintype "passive"))
      (node (ref "R109") (pin "2") (pinfunction "2_2") (pintype "passive"))
      (node (ref "R110") (pin "1") (pinfunction "1_1") (pintype "passive"))
      (node (ref "R203") (pin "1") (pinfunction "1_1") (pintype "passive"))
      (node (ref "R204") (pin "2") (pinfunction "2_2") (pintype "passive"))
      (node (ref "R206") (pin "1") (pinfunction "1_1") (pintype "passive"))
      (node (ref "R209") (pin "2") (pinfunction "2_2") (pintype "passive"))
      (node (ref "R303") (pin "1") (pinfunction "1_1") (pintype "passive"))
      (node (ref "R304") (pin "1") (pinfunction "1_1") (pintype "passive"))
      (node (ref "R317") (pin "1") (pinfunction "1_1") (pintype "passive"))
      (node (ref "R318") (pin "1") (pinfunction "1_1") (pintype "passive"))
      (node (ref "S100") (pin "1") (pinfunction "1_1") (pintype "passive"))
      (node (ref "S100") (pin "2") (pinfunction "2_2") (pintype "passive"))
      (node (ref "TP300") (pin "X") (pinfunction "TESTP_X") (pintype "passive"))
      (node (ref "TR3") (pin "2") (pinfunction "S_2") (pintype "passive"))
      (node (ref "U200") (pin "2") (pinfunction "GND_2") (pintype "power_in"))
      (node (ref "U201") (pin "1") (pinfunction "GND_1") (pintype "passive"))
      (node (ref "XC100") (pin "P$1") (pinfunction "GND_P$1") (pintype "bidirectional"))
    )
    (net (code "21") (name "MISO") (class "Default")
      (node (ref "IC2") (pin "28") (pinfunction "PA19/EIC/SCOM1PAD3+/TC3_28") (pintype "bidirectional"))
      (node (ref "J101") (pin "5") (pinfunction "5_5") (pintype "passive"))
      (node (ref "R311") (pin "2") (pinfunction "2_2") (pintype "passive"))
    )
    (net (code "22") (name "MOSI") (class "Default")
      (node (ref "IC2") (pin "25") (pinfunction "PA16/I2C/EIC/SCOM1PAD0+/TC2_25") (pintype "bidirectional"))
      (node (ref "J101") (pin "4") (pinfunction "4_4") (pintype "passive"))
      (node (ref "R312") (pin "2") (pinfunction "2_2") (pintype "passive"))
    )
    (net (code "23") (name "Net-(C109-Pad2)") (class "Default")
      (node (ref "C109") (pin "2") (pinfunction "2_2") (pintype "passive"))
      (node (ref "J107") (pin "SHLD1") (pinfunction "SH_SHLD1") (pintype "bidirectional"))
      (node (ref "J107") (pin "SHLD2") (pinfunction "SH_SHLD2") (pintype "bidirectional"))
      (node (ref "J107") (pin "SHLD3") (pinfunction "SH_SHLD3") (pintype "bidirectional"))
      (node (ref "J107") (pin "SHLD4") (pinfunction "SH_SHLD4") (pintype "bidirectional"))
      (node (ref "J107") (pin "SHLD5") (pinfunction "SH_SHLD5") (pintype "bidirectional"))
      (node (ref "J107") (pin "SHLD6") (pinfunction "SH_SHLD6") (pintype "bidirectional"))
      (node (ref "R110") (pin "2") (pinfunction "2_2") (pintype "passive"))
    )
    (net (code "24") (name "Net-(C111-Pad2)") (class "Default")
      (node (ref "C111") (pin "2") (pinfunction "2_2") (pintype "passive"))
      (node (ref "F100") (pin "1") (pinfunction "1_1") (pintype "passive"))
      (node (ref "L101") (pin "2") (pinfunction "2_2") (pintype "passive"))
    )
    (net (code "25") (name "Net-(C303-Pad2)") (class "Default")
      (node (ref "C303") (pin "2") (pinfunction "2_2") (pintype "passive"))
      (node (ref "J300") (pin "SHLD1") (pinfunction "SH_SHLD1") (pintype "bidirectional"))
      (node (ref "J300") (pin "SHLD2") (pinfunction "SH_SHLD2") (pintype "bidirectional"))
      (node (ref "J300") (pin "SHLD3") (pinfunction "SH_SHLD3") (pintype "bidirectional"))
      (node (ref "J300") (pin "SHLD4") (pinfunction "SH_SHLD4") (pintype "bidirectional"))
      (node (ref "J300") (pin "SHLD5") (pinfunction "SH_SHLD5") (pintype "bidirectional"))
      (node (ref "J300") (pin "SHLD6") (pinfunction "SH_SHLD6") (pintype "bidirectional"))
      (node (ref "R318") (pin "2") (pinfunction "2_2") (pintype "passive"))
    )
    (net (code "26") (name "Net-(C308-Pad1)") (class "Default")
      (node (ref "C308") (pin "1") (pinfunction "1_1") (pintype "passive"))
      (node (ref "F300") (pin "1") (pinfunction "1_1") (pintype "passive"))
      (node (ref "L300") (pin "2") (pinfunction "2_2") (pintype "passive"))
    )
    (net (code "27") (name "Net-(D101-PadA)") (class "Default")
      (node (ref "D101") (pin "A") (pinfunction "A_A") (pintype "passive"))
      (node (ref "R107") (pin "2") (pinfunction "2_2") (pintype "passive"))
    )
    (net (code "28") (name "Net-(D102-PadA)") (class "Default")
      (node (ref "D102") (pin "A") (pinfunction "A_A") (pintype "passive"))
      (node (ref "R108") (pin "2") (pinfunction "2_2") (pintype "passive"))
    )
    (net (code "29") (name "Net-(D201-PadC)") (class "Default")
      (node (ref "D201") (pin "C") (pinfunction "C_C") (pintype "passive"))
      (node (ref "L200") (pin "1") (pinfunction "1_1") (pintype "passive"))
    )
    (net (code "30") (name "Net-(D300-PadA)") (class "Default")
      (node (ref "D300") (pin "A") (pinfunction "A_A") (pintype "passive"))
      (node (ref "R301") (pin "1") (pinfunction "1_1") (pintype "passive"))
    )
    (net (code "31") (name "Net-(D301-PadA)") (class "Default")
      (node (ref "D301") (pin "A") (pinfunction "A_A") (pintype "passive"))
      (node (ref "R302") (pin "1") (pinfunction "1_1") (pintype "passive"))
    )
    (net (code "32") (name "Net-(EDBG-DMF_S)") (class "Default")
      (node (ref "EDBG") (pin "B9") (pinfunction "DMF_S_B9") (pintype "bidirectional"))
      (node (ref "R315") (pin "2") (pinfunction "2_2") (pintype "passive"))
    )
    (net (code "33") (name "Net-(EDBG-DPF_S)") (class "Default")
      (node (ref "EDBG") (pin "B8") (pinfunction "DPF_S_B8") (pintype "bidirectional"))
      (node (ref "R316") (pin "2") (pinfunction "2_2") (pintype "passive"))
    )
    (net (code "34") (name "Net-(EDBG-PA03)") (class "Default")
      (node (ref "EDBG") (pin "F9") (pinfunction "PA03_F9") (pintype "bidirectional"))
      (node (ref "R305") (pin "2") (pinfunction "2_2") (pintype "passive"))
    )
    (net (code "35") (name "Net-(EDBG-PA04)") (class "Default")
      (node (ref "EDBG") (pin "E9") (pinfunction "PA04_E9") (pintype "bidirectional"))
      (node (ref "R306") (pin "2") (pinfunction "2_2") (pintype "passive"))
    )
    (net (code "36") (name "Net-(EDBG-PA08)") (class "Default")
      (node (ref "EDBG") (pin "F8") (pinfunction "PA08_F8") (pintype "bidirectional"))
      (node (ref "R307") (pin "2") (pinfunction "2_2") (pintype "passive"))
    )
    (net (code "37") (name "Net-(EDBG-PA09)") (class "Default")
      (node (ref "EDBG") (pin "D8") (pinfunction "PA09_D8") (pintype "bidirectional"))
      (node (ref "R308") (pin "2") (pinfunction "2_2") (pintype "passive"))
    )
    (net (code "38") (name "Net-(EDBG-PA10)") (class "Default")
      (node (ref "EDBG") (pin "C10") (pinfunction "PA10_C10") (pintype "bidirectional"))
      (node (ref "R309") (pin "2") (pinfunction "2_2") (pintype "passive"))
    )
    (net (code "39") (name "Net-(EDBG-PA11)") (class "Default")
      (node (ref "EDBG") (pin "C9") (pinfunction "PA11_C9") (pintype "bidirectional"))
      (node (ref "R310") (pin "2") (pinfunction "2_2") (pintype "passive"))
    )
    (net (code "40") (name "Net-(EDBG-PC02)") (class "Default")
      (node (ref "C300") (pin "1") (pinfunction "1_1") (pintype "passive"))
      (node (ref "EDBG") (pin "A5") (pinfunction "PC02_A5") (pintype "bidirectional"))
      (node (ref "X300") (pin "3") (pinfunction "C2_3") (pintype "passive"))
    )
    (net (code "41") (name "Net-(EDBG-PC03)") (class "Default")
      (node (ref "C301") (pin "1") (pinfunction "1_1") (pintype "passive"))
      (node (ref "EDBG") (pin "A6") (pinfunction "PC03_A6") (pintype "bidirectional"))
      (node (ref "X300") (pin "1") (pinfunction "C1_1") (pintype "passive"))
    )
    (net (code "42") (name "Net-(EDBG-PX27)") (class "Default")
      (node (ref "EDBG") (pin "K2") (pinfunction "PX27_K2") (pintype "bidirectional"))
      (node (ref "R311") (pin "1") (pinfunction "1_1") (pintype "passive"))
    )
    (net (code "43") (name "Net-(EDBG-PX28)") (class "Default")
      (node (ref "EDBG") (pin "K3") (pinfunction "PX28_K3") (pintype "bidirectional"))
      (node (ref "R312") (pin "1") (pinfunction "1_1") (pintype "passive"))
    )
    (net (code "44") (name "Net-(EDBG-PX29)") (class "Default")
      (node (ref "EDBG") (pin "J4") (pinfunction "PX29_J4") (pintype "bidirectional"))
      (node (ref "R313") (pin "1") (pinfunction "1_1") (pintype "passive"))
    )
    (net (code "45") (name "Net-(EDBG-PX30)") (class "Default")
      (node (ref "EDBG") (pin "G5") (pinfunction "PX30_G5") (pintype "bidirectional"))
      (node (ref "R314") (pin "1") (pinfunction "1_1") (pintype "passive"))
    )
    (net (code "46") (name "Net-(EDBG-USB_VBIAS)") (class "Default")
      (node (ref "C302") (pin "1") (pinfunction "1_1") (pintype "passive"))
      (node (ref "EDBG") (pin "C7") (pinfunction "USB_VBIAS_C7") (pintype "bidirectional"))
      (node (ref "R317") (pin "2") (pinfunction "2_2") (pintype "passive"))
    )
    (net (code "47") (name "Net-(EDBG-VDDANA)") (class "Default")
      (node (ref "C304") (pin "1") (pinfunction "1_1") (pintype "passive"))
      (node (ref "EDBG") (pin "J6") (pinfunction "VDDANA_J6") (pintype "bidirectional"))
      (node (ref "L301") (pin "2") (pinfunction "2_2") (pintype "passive"))
    )
    (net (code "48") (name "Net-(EDBG-VDDCORE)") (class "Default")
      (node (ref "C305") (pin "1") (pinfunction "1_1") (pintype "passive"))
      (node (ref "C306") (pin "1") (pinfunction "1_1") (pintype "passive"))
      (node (ref "EDBG") (pin "E10") (pinfunction "VDDCORE_E10") (pintype "bidirectional"))
    )
    (net (code "49") (name "Net-(IC2-VDDANA)") (class "Default")
      (node (ref "C106") (pin "1") (pinfunction "1_1") (pintype "passive"))
      (node (ref "C107") (pin "1") (pinfunction "1_1") (pintype "passive"))
      (node (ref "IC2") (pin "6") (pinfunction "VDDANA_6") (pintype "power_in"))
      (node (ref "L100") (pin "1") (pinfunction "1_1") (pintype "passive"))
    )
    (net (code "50") (name "Net-(J107-VUSB)") (class "Default")
      (node (ref "C110") (pin "2") (pinfunction "2_2") (pintype "passive"))
      (node (ref "D103") (pin "4") (pinfunction "4_4") (pintype "bidirectional"))
      (node (ref "J107") (pin "VBUS") (pinfunction "VUSB_VBUS") (pintype "bidirectional"))
      (node (ref "L101") (pin "1") (pinfunction "1_1") (pintype "passive"))
    )
    (net (code "51") (name "Net-(LED3-PadA)") (class "Default")
      (node (ref "LED3") (pin "A") (pinfunction "A_A") (pintype "passive"))
      (node (ref "R106") (pin "2") (pinfunction "2_2") (pintype "passive"))
    )
    (net (code "52") (name "Net-(Q201-S)") (class "Default")
      (node (ref "Q201") (pin "2") (pinfunction "S_2") (pintype "passive"))
      (node (ref "R207") (pin "1") (pinfunction "1_1") (pintype "passive"))
      (node (ref "R208") (pin "1") (pinfunction "1_1") (pintype "passive"))
    )
    (net (code "53") (name "Net-(Q202-G)") (class "Default")
      (node (ref "Q202") (pin "1") (pinfunction "G_1") (pintype "passive"))
      (node (ref "Q203") (pin "2") (pinfunction "S_2") (pintype "passive"))
      (node (ref "R209") (pin "1") (pinfunction "1_1") (pintype "passive"))
    )
    (net (code "54") (name "Net-(Q300A-D)") (class "Default")
      (node (ref "D301") (pin "C") (pinfunction "C_C") (pintype "passive"))
      (node (ref "Q300") (pin "3") (pinfunction "D_3") (pintype "passive"))
    )
    (net (code "55") (name "Net-(Q300B-D)") (class "Default")
      (node (ref "D300") (pin "C") (pinfunction "C_C") (pintype "passive"))
      (node (ref "Q300") (pin "6") (pinfunction "D_6") (pintype "passive"))
      (node (ref "R303") (pin "2") (pinfunction "2_2") (pintype "passive"))
    )
    (net (code "56") (name "Net-(R102-Pad1)") (class "Default")
      (node (ref "R102") (pin "1") (pinfunction "1_1") (pintype "passive"))
      (node (ref "S100") (pin "3") (pinfunction "3_3") (pintype "passive"))
      (node (ref "S100") (pin "4") (pinfunction "4_4") (pintype "passive"))
    )
    (net (code "57") (name "Net-(TR3-D)") (class "Default")
      (node (ref "LED3") (pin "C") (pinfunction "C_C") (pintype "passive"))
      (node (ref "TR3") (pin "1") (pinfunction "D_1") (pintype "passive"))
    )
    (net (code "58") (name "PA00_XIN32") (class "Default")
      (node (ref "C103") (pin "2") (pinfunction "2_2") (pintype "passive"))
      (node (ref "IC2") (pin "1") (pinfunction "PA0/XIN32/EIC/SCOM1PAD0/TC2_1") (pintype "bidirectional"))
      (node (ref "XC100") (pin "2") (pinfunction "2_2") (pintype "passive"))
    )
    (net (code "59") (name "PA01_XOUT32") (class "Default")
      (node (ref "C104") (pin "2") (pinfunction "2_2") (pintype "passive"))
      (node (ref "IC2") (pin "2") (pinfunction "PA1/XOUT32/EIC/SCOM1PAD1/TC2_2") (pintype "bidirectional"))
      (node (ref "J103") (pin "1") (pinfunction "1_1") (pintype "passive"))
      (node (ref "J103") (pin "2") (pinfunction "2_2") (pintype "passive"))
      (node (ref "XC100") (pin "1") (pinfunction "1_1") (pintype "passive"))
    )
    (net (code "60") (name "PA02_AIN0") (class "Default")
      (node (ref "IC2") (pin "3") (pinfunction "PA2/EIC/AIN0_3") (pintype "bidirectional"))
      (node (ref "J106") (pin "1") (pinfunction "1_1") (pintype "passive"))
    )
    (net (code "61") (name "PA03_AREFA") (class "Default")
      (node (ref "C112") (pin "1") (pinfunction "1_1") (pintype "passive"))
      (node (ref "C113") (pin "1") (pinfunction "1_1") (pintype "passive"))
      (node (ref "IC2") (pin "4") (pinfunction "PA3/EIC/REF/AIN1_4") (pintype "bidirectional"))
      (node (ref "J101") (pin "8") (pinfunction "8_8") (pintype "passive"))
    )
    (net (code "62") (name "PA04_AIN4") (class "Default")
      (node (ref "IC2") (pin "9") (pinfunction "PA4/EIC/REF/AIN4/SCOM0PAD0/TC0_9") (pintype "bidirectional"))
      (node (ref "J106") (pin "4") (pinfunction "4_4") (pintype "passive"))
    )
    (net (code "63") (name "PA05_AIN5") (class "Default")
      (node (ref "IC2") (pin "10") (pinfunction "PA5/EIC/AIN5/SCOM0PAD1/TC0_10") (pintype "bidirectional"))
      (node (ref "J106") (pin "5") (pinfunction "5_5") (pintype "passive"))
    )
    (net (code "64") (name "PA08_TCC0-W0") (class "Default")
      (node (ref "IC2") (pin "23") (pinfunction "PA14/XIN/EIC/SCOM2PAD2+/TC3_23") (pintype "bidirectional"))
      (node (ref "J102") (pin "5") (pinfunction "5_5") (pintype "passive"))
    )
    (net (code "65") (name "PA09_TCC0-W1") (class "Default")
      (node (ref "IC2") (pin "14") (pinfunction "PA9/I2C/EIC/AIN17/SCOM2PAD1+/TC0_14") (pintype "bidirectional"))
      (node (ref "J102") (pin "4") (pinfunction "4_4") (pintype "passive"))
    )
    (net (code "66") (name "PA10_TCC0-W2") (class "Default")
      (node (ref "IC2") (pin "15") (pinfunction "PA10/EIC/AIN18/SCOM2PAD2+/TC1_15") (pintype "bidirectional"))
      (node (ref "J102") (pin "2") (pinfunction "2_2") (pintype "passive"))
    )
    (net (code "67") (name "PA11_TCC0-W3") (class "Default")
      (node (ref "IC2") (pin "16") (pinfunction "PA11/EIC/AIN19/SCOM2PAD3+/TC1_16") (pintype "bidirectional"))
      (node (ref "J102") (pin "1") (pinfunction "1_1") (pintype "passive"))
    )
    (net (code "68") (name "PA13_GPIO") (class "Default")
      (node (ref "IC2") (pin "22") (pinfunction "PA13/I2C/EIC/SCOM2PAD1+/TC2_22") (pintype "bidirectional"))
    )
    (net (code "69") (name "PA14_TCC0-W4") (class "Default")
      (node (ref "IC2") (pin "13") (pinfunction "PA8/I2C/AIN16/SCOM2PAD0+/TC0_13") (pintype "bidirectional"))
      (node (ref "J102") (pin "3") (pinfunction "3_3") (pintype "passive"))
    )
    (net (code "70") (name "PA15_TCC0-W5") (class "Default")
      (node (ref "IC2") (pin "24") (pinfunction "PA15/XOUT/EIC/SCOM2PAD3+/TC3_24") (pintype "bidirectional"))
      (node (ref "J102") (pin "6") (pinfunction "6_6") (pintype "passive"))
    )
    (net (code "71") (name "PA20_TCC0-W6") (class "Default")
      (node (ref "IC2") (pin "29") (pinfunction "PA20/EIC/SCOM5PAD2+_29") (pintype "bidirectional"))
      (node (ref "J102") (pin "7") (pinfunction "7_7") (pintype "passive"))
    )
    (net (code "72") (name "PA27_TX_LED") (class "Default")
      (node (ref "D102") (pin "C") (pinfunction "C_C") (pintype "passive"))
      (node (ref "IC2") (pin "39") (pinfunction "PA27/EIC_39") (pintype "bidirectional"))
    )
    (net (code "73") (name "PA28_USB_HOST_EN") (class "Default")
      (node (ref "IC2") (pin "41") (pinfunction "PA28/EIC_41") (pintype "bidirectional"))
      (node (ref "R113") (pin "2") (pinfunction "2_2") (pintype "passive"))
    )
    (net (code "74") (name "PA30_SWCLK") (class "Default")
      (node (ref "IC2") (pin "45") (pinfunction "PA30/EIC/SCOM1PAD2/TC1_45") (pintype "bidirectional"))
      (node (ref "R104") (pin "1") (pinfunction "1_1") (pintype "passive"))
    )
    (net (code "75") (name "PA31_SWDIO") (class "Default")
      (node (ref "IC2") (pin "46") (pinfunction "PA31/EIC/SCOM1PAD3/TC1_46") (pintype "bidirectional"))
      (node (ref "R105") (pin "2") (pinfunction "2_2") (pintype "passive"))
    )
    (net (code "76") (name "PB02_AIN10") (class "Default")
      (node (ref "IC2") (pin "47") (pinfunction "PB2/EIC/AIN10/SCOM5PAD0_47") (pintype "bidirectional"))
      (node (ref "J106") (pin "6") (pinfunction "6_6") (pintype "passive"))
    )
    (net (code "77") (name "PB03_RX_LED") (class "Default")
      (node (ref "D101") (pin "C") (pinfunction "C_C") (pintype "passive"))
      (node (ref "IC2") (pin "48") (pinfunction "PB3/EIC/AIN11/SCOM5PAD1_48") (pintype "bidirectional"))
    )
    (net (code "78") (name "PB08_AIN2") (class "Default")
      (node (ref "IC2") (pin "7") (pinfunction "PB8/EIC/AIN2/SCOM4PAD0/TC4_7") (pintype "bidirectional"))
      (node (ref "J106") (pin "2") (pinfunction "2_2") (pintype "passive"))
    )
    (net (code "79") (name "PB09_AIN3") (class "Default")
      (node (ref "IC2") (pin "8") (pinfunction "PB9/EIC/AIN3/SCOM4PAD1//TC4_8") (pintype "bidirectional"))
      (node (ref "J106") (pin "3") (pinfunction "3_3") (pintype "passive"))
    )
    (net (code "80") (name "PB10_S4_SPI_MOSI") (class "Default")
      (node (ref "IC2") (pin "19") (pinfunction "PB10/EIC/SCOM4PAD2/TC5_19") (pintype "bidirectional"))
      (node (ref "ICSP") (pin "4") (pinfunction "4_4") (pintype "passive"))
    )
    (net (code "81") (name "PB11_S4_SPI_SCK") (class "Default")
      (node (ref "IC2") (pin "20") (pinfunction "PB11/EIC/SCOM4PAD3/TC5_20") (pintype "bidirectional"))
      (node (ref "ICSP") (pin "3") (pinfunction "3_3") (pintype "passive"))
    )
    (net (code "82") (name "PB12_S4_SPI_MISO") (class "Default")
      (node (ref "IC2") (pin "21") (pinfunction "PA12/I2C/EIC/SCOM2PAD0+/TC2_21") (pintype "bidirectional"))
      (node (ref "ICSP") (pin "1") (pinfunction "1_1") (pintype "passive"))
    )
    (net (code "83") (name "POWER_LED_CTRL") (class "Default")
      (node (ref "EDBG") (pin "K4") (pinfunction "PX32/PX15_K4") (pintype "bidirectional"))
      (node (ref "Q300") (pin "2") (pinfunction "G_2") (pintype "passive"))
      (node (ref "R300") (pin "1") (pinfunction "1_1") (pintype "passive"))
    )
    (net (code "84") (name "RXD") (class "Default")
      (node (ref "IC2") (pin "38") (pinfunction "PB23/EIC/SCOM5PAD3_38") (pintype "bidirectional"))
      (node (ref "R306") (pin "1") (pinfunction "1_1") (pintype "passive"))
    )
    (net (code "85") (name "SAMD21_RESET") (class "Default")
      (node (ref "EDBG") (pin "B4") (pinfunction "PA29_B4") (pintype "bidirectional"))
      (node (ref "IC2") (pin "40") (pinfunction "RESETN_40") (pintype "bidirectional"))
      (node (ref "R103") (pin "1") (pinfunction "1_1") (pintype "passive"))
    )
    (net (code "86") (name "SCK") (class "Default")
      (node (ref "IC2") (pin "26") (pinfunction "PA17/I2C/EIC/SCOM1PAD1+/TC2_26") (pintype "bidirectional"))
      (node (ref "J101") (pin "6") (pinfunction "6_6") (pintype "passive"))
      (node (ref "R109") (pin "1") (pinfunction "1_1") (pintype "passive"))
      (node (ref "R313") (pin "2") (pinfunction "2_2") (pintype "passive"))
      (node (ref "TR3") (pin "3") (pinfunction "G_3") (pintype "passive"))
    )
    (net (code "87") (name "SCL") (class "Default")
      (node (ref "EDBG") (pin "F7") (pinfunction "PA26/PB05_F7") (pintype "bidirectional"))
      (node (ref "IC2") (pin "32") (pinfunction "PA23/I2C/EIC/SCOM5PAD1+/TC4_32") (pintype "bidirectional"))
      (node (ref "J101") (pin "10") (pinfunction "10_10") (pintype "passive"))
      (node (ref "R112") (pin "1") (pinfunction "1_1") (pintype "passive"))
    )
    (net (code "88") (name "SDA") (class "Default")
      (node (ref "EDBG") (pin "G7") (pinfunction "PA12/PA25_G7") (pintype "bidirectional"))
      (node (ref "IC2") (pin "31") (pinfunction "PA22/I2C/EIC/SCOM5PAD0+/TC4_31") (pintype "bidirectional"))
      (node (ref "J101") (pin "9") (pinfunction "9_9") (pintype "passive"))
      (node (ref "R111") (pin "1") (pinfunction "1_1") (pintype "passive"))
    )
    (net (code "89") (name "SS") (class "Default")
      (node (ref "IC2") (pin "27") (pinfunction "PA18/EIC/SCOM1PAD2+/TC3_27") (pintype "bidirectional"))
      (node (ref "J101") (pin "3") (pinfunction "3_3") (pintype "passive"))
      (node (ref "R314") (pin "2") (pinfunction "2_2") (pintype "passive"))
    )
    (net (code "90") (name "STATUS_LED_CTRL") (class "Default")
      (node (ref "EDBG") (pin "F1") (pinfunction "PX59/PX19_F1") (pintype "bidirectional"))
      (node (ref "Q300") (pin "5") (pinfunction "G_5") (pintype "passive"))
      (node (ref "R304") (pin "2") (pinfunction "2_2") (pintype "passive"))
    )
    (net (code "91") (name "SW") (class "Default")
      (node (ref "C200") (pin "2") (pinfunction "2_2") (pintype "passive"))
      (node (ref "D202") (pin "P$1") (pinfunction "K_P$1") (pintype "bidirectional"))
      (node (ref "L201") (pin "P$1") (pinfunction "1_P$1") (pintype "passive"))
      (node (ref "U200") (pin "6") (pinfunction "SW_6") (pintype "output"))
    )
    (net (code "92") (name "SWCLK") (class "Default")
      (node (ref "EDBG") (pin "D6") (pinfunction "PB07_D6") (pintype "bidirectional"))
      (node (ref "J100") (pin "4") (pinfunction "4_4") (pintype "passive"))
      (node (ref "R104") (pin "2") (pinfunction "2_2") (pintype "passive"))
    )
    (net (code "93") (name "SWDIO") (class "Default")
      (node (ref "EDBG") (pin "C5") (pinfunction "PB09_C5") (pintype "bidirectional"))
      (node (ref "J100") (pin "2") (pinfunction "2_2") (pintype "passive"))
      (node (ref "R105") (pin "1") (pinfunction "1_1") (pintype "passive"))
    )
    (net (code "94") (name "TARGET_RESET") (class "Default")
      (node (ref "C101") (pin "1") (pinfunction "1_1") (pintype "passive"))
      (node (ref "ICSP") (pin "5") (pinfunction "5_5") (pintype "passive"))
      (node (ref "J100") (pin "10") (pinfunction "10_10") (pintype "passive"))
      (node (ref "J105") (pin "3") (pinfunction "3_3") (pintype "passive"))
      (node (ref "R100") (pin "1") (pinfunction "1_1") (pintype "passive"))
      (node (ref "R101") (pin "2") (pinfunction "2_2") (pintype "passive"))
      (node (ref "R102") (pin "2") (pinfunction "2_2") (pintype "passive"))
      (node (ref "R103") (pin "2") (pinfunction "2_2") (pintype "passive"))
    )
    (net (code "95") (name "TARGET_RESET_SENSE") (class "Default")
      (node (ref "EDBG") (pin "H2") (pinfunction "PX21_H2") (pintype "bidirectional"))
      (node (ref "R101") (pin "1") (pinfunction "1_1") (pintype "passive"))
    )
    (net (code "96") (name "TARGET_USB_N") (class "Default")
      (node (ref "D103") (pin "3") (pinfunction "3_3") (pintype "bidirectional"))
      (node (ref "IC2") (pin "33") (pinfunction "PA24/EIC/SCOM3PAD2+/TC5_33") (pintype "bidirectional"))
      (node (ref "J107") (pin "D-") (pinfunction "D-_D-") (pintype "bidirectional"))
    )
    (net (code "97") (name "TARGET_USB_P") (class "Default")
      (node (ref "D103") (pin "2") (pinfunction "2_2") (pintype "bidirectional"))
      (node (ref "IC2") (pin "34") (pinfunction "PA25/EIC/SCOM3PAD3+/TC5_34") (pintype "bidirectional"))
      (node (ref "J107") (pin "D+") (pinfunction "D+_D+") (pintype "bidirectional"))
    )
    (net (code "98") (name "TXD") (class "Default")
      (node (ref "IC2") (pin "37") (pinfunction "PB22/EIC/SCOM5PAD2_37") (pintype "bidirectional"))
      (node (ref "R305") (pin "1") (pinfunction "1_1") (pintype "passive"))
    )
    (net (code "99") (name "USB_HOST_ENABLE") (class "Default")
      (node (ref "J107") (pin "ID") (pinfunction "ID_ID") (pintype "bidirectional"))
      (node (ref "Q203") (pin "1") (pinfunction "G_1") (pintype "passive"))
      (node (ref "R113") (pin "1") (pinfunction "1_1") (pintype "passive"))
      (node (ref "R210") (pin "2") (pinfunction "2_2") (pintype "passive"))
    )
    (net (code "100") (name "VCC_EDBG_3V3") (class "Default")
      (node (ref "C309") (pin "1") (pinfunction "1_1") (pintype "passive"))
      (node (ref "C310") (pin "1") (pinfunction "1_1") (pintype "passive"))
      (node (ref "C311") (pin "1") (pinfunction "1_1") (pintype "passive"))
      (node (ref "C312") (pin "1") (pinfunction "1_1") (pintype "passive"))
      (node (ref "C313") (pin "1") (pinfunction "1_1") (pintype "passive"))
      (node (ref "C314") (pin "1") (pinfunction "1_1") (pintype "passive"))
      (node (ref "C315") (pin "1") (pinfunction "1_1") (pintype "passive"))
      (node (ref "EDBG") (pin "B5") (pinfunction "VDDIO_B5") (pintype "bidirectional"))
      (node (ref "EDBG") (pin "B6") (pinfunction "VDDIO1_B6") (pintype "bidirectional"))
      (node (ref "EDBG") (pin "D10") (pinfunction "VDDIN1_D10") (pintype "bidirectional"))
      (node (ref "EDBG") (pin "D9") (pinfunction "VDDIN_D9") (pintype "bidirectional"))
      (node (ref "EDBG") (pin "E5") (pinfunction "VDDIO2_E5") (pintype "bidirectional"))
      (node (ref "EDBG") (pin "F2") (pinfunction "VDDIO3_F2") (pintype "bidirectional"))
      (node (ref "EDBG") (pin "F6") (pinfunction "VDDIO4_F6") (pintype "bidirectional"))
      (node (ref "EDBG") (pin "J5") (pinfunction "VDDIO5_J5") (pintype "bidirectional"))
      (node (ref "J301") (pin "4") (pinfunction "4_4") (pintype "passive"))
      (node (ref "L301") (pin "1") (pinfunction "1_1") (pintype "passive"))
      (node (ref "R300") (pin "2") (pinfunction "2_2") (pintype "passive"))
      (node (ref "R301") (pin "2") (pinfunction "2_2") (pintype "passive"))
      (node (ref "R302") (pin "2") (pinfunction "2_2") (pintype "passive"))
      (node (ref "R319") (pin "2") (pinfunction "2_2") (pintype "passive"))
    )
    (net (code "101") (name "VCC_EDBG_USB") (class "Default")
      (node (ref "EDBG") (pin "A10") (pinfunction "USB_VBUS_A10") (pintype "bidirectional"))
      (node (ref "F300") (pin "2") (pinfunction "2_2") (pintype "passive"))
      (node (ref "Q200") (pin "3") (pinfunction "D_3") (pintype "passive"))
      (node (ref "Q201") (pin "1") (pinfunction "D_1") (pintype "passive"))
      (node (ref "R208") (pin "2") (pinfunction "2_2") (pintype "passive"))
    )
    (net (code "102") (name "VCC_EXT_VIN") (class "Default")
      (node (ref "C203") (pin "+") (pinfunction "+_+") (pintype "passive"))
      (node (ref "J105") (pin "8") (pinfunction "8_8") (pintype "passive"))
      (node (ref "L200") (pin "2") (pinfunction "2_2") (pintype "passive"))
      (node (ref "R200") (pin "1") (pinfunction "1_1") (pintype "passive"))
      (node (ref "U200") (pin "5") (pinfunction "VIN_5") (pintype "input"))
    )
    (net (code "103") (name "VDDCORE") (class "Default")
      (node (ref "C102") (pin "1") (pinfunction "1_1") (pintype "passive"))
      (node (ref "IC2") (pin "43") (pinfunction "VDDCORE1_43") (pintype "input"))
    )
    (net (code "104") (name "VEXT") (class "Default")
      (node (ref "D201") (pin "A") (pinfunction "A_A") (pintype "passive"))
      (node (ref "J200") (pin "2") (pinfunction "2_2") (pintype "power_in"))
      (node (ref "R205") (pin "2") (pinfunction "2_2") (pintype "passive"))
    )
    (net (code "105") (name "VIN_DETECT") (class "Default")
      (node (ref "Q200") (pin "1") (pinfunction "G_1") (pintype "passive"))
      (node (ref "R205") (pin "1") (pinfunction "1_1") (pintype "passive"))
      (node (ref "R206") (pin "2") (pinfunction "2_2") (pintype "passive"))
    )
    (net (code "106") (name "XVCC") (class "Default")
      (node (ref "C307") (pin "1") (pinfunction "1_1") (pintype "passive"))
      (node (ref "D302") (pin "4") (pinfunction "4_4") (pintype "bidirectional"))
      (node (ref "J300") (pin "VBUS") (pinfunction "VUSB_VBUS") (pintype "bidirectional"))
      (node (ref "L300") (pin "1") (pinfunction "1_1") (pintype "passive"))
    )
    (net (code "107") (name "unconnected-(EDBG-PA00{slash}PA18-PadG8)") (class "Default")
      (node (ref "EDBG") (pin "G8") (pinfunction "PA00/PA18_G8") (pintype "bidirectional"))
    )
    (net (code "108") (name "unconnected-(EDBG-PA01{slash}PA17-PadG10)") (class "Default")
      (node (ref "EDBG") (pin "G10") (pinfunction "PA01/PA17_G10") (pintype "bidirectional"))
    )
    (net (code "109") (name "unconnected-(EDBG-PA02{slash}PX47-PadE1)") (class "Default")
      (node (ref "EDBG") (pin "E1") (pinfunction "PA02/PX47_E1") (pintype "bidirectional"))
    )
    (net (code "110") (name "unconnected-(EDBG-PA05-PadG9)") (class "Default")
      (node (ref "EDBG") (pin "G9") (pinfunction "PA05_G9") (pintype "bidirectional"))
    )
    (net (code "111") (name "unconnected-(EDBG-PA06{slash}PA13-PadE8)") (class "Default")
      (node (ref "EDBG") (pin "E8") (pinfunction "PA06/PA13_E8") (pintype "bidirectional"))
    )
    (net (code "112") (name "unconnected-(EDBG-PA07{slash}PA19-PadH10)") (class "Default")
      (node (ref "EDBG") (pin "H10") (pinfunction "PA07/PA19_H10") (pintype "bidirectional"))
    )
    (net (code "113") (name "unconnected-(EDBG-PA14{slash}PX11-PadK7)") (class "Default")
      (node (ref "EDBG") (pin "K7") (pinfunction "PA14/PX11_K7") (pintype "bidirectional"))
    )
    (net (code "114") (name "unconnected-(EDBG-PA15{slash}PX45-PadJ7)") (class "Default")
      (node (ref "EDBG") (pin "J7") (pinfunction "PA15/PX45_J7") (pintype "bidirectional"))
    )
    (net (code "115") (name "unconnected-(EDBG-PA16-PadE7)") (class "Default")
      (node (ref "EDBG") (pin "E7") (pinfunction "PA16_E7") (pintype "bidirectional"))
    )
    (net (code "116") (name "unconnected-(EDBG-PA22{slash}PX20-PadH6)") (class "Default")
      (node (ref "EDBG") (pin "H6") (pinfunction "PA22/PX20_H6") (pintype "bidirectional"))
    )
    (net (code "117") (name "unconnected-(EDBG-PA23{slash}PX46-PadG6)") (class "Default")
      (node (ref "EDBG") (pin "G6") (pinfunction "PA23/PX46_G6") (pintype "bidirectional"))
    )
    (net (code "118") (name "unconnected-(EDBG-PA24{slash}PX17-PadJ10)") (class "Default")
      (node (ref "EDBG") (pin "J10") (pinfunction "PA24/PX17_J10") (pintype "bidirectional"))
    )
    (net (code "119") (name "unconnected-(EDBG-PA27-PadA2)") (class "Default")
      (node (ref "EDBG") (pin "A2") (pinfunction "PA27_A2") (pintype "bidirectional"))
    )
    (net (code "120") (name "unconnected-(EDBG-PA28-PadA1)") (class "Default")
      (node (ref "EDBG") (pin "A1") (pinfunction "PA28_A1") (pintype "bidirectional"))
    )
    (net (code "121") (name "unconnected-(EDBG-PA30-PadA4)") (class "Default")
      (node (ref "EDBG") (pin "A4") (pinfunction "PA30_A4") (pintype "bidirectional"))
    )
    (net (code "122") (name "unconnected-(EDBG-PA31-PadC2)") (class "Default")
      (node (ref "EDBG") (pin "C2") (pinfunction "PA31_C2") (pintype "bidirectional"))
    )
    (net (code "123") (name "unconnected-(EDBG-PB00-PadB1)") (class "Default")
      (node (ref "EDBG") (pin "B1") (pinfunction "PB00_B1") (pintype "bidirectional"))
    )
    (net (code "124") (name "unconnected-(EDBG-PB01-PadB2)") (class "Default")
      (node (ref "EDBG") (pin "B2") (pinfunction "PB01_B2") (pintype "bidirectional"))
    )
    (net (code "125") (name "unconnected-(EDBG-PB02-PadB3)") (class "Default")
      (node (ref "EDBG") (pin "B3") (pinfunction "PB02_B3") (pintype "bidirectional"))
    )
    (net (code "126") (name "unconnected-(EDBG-PB03-PadC4)") (class "Default")
      (node (ref "EDBG") (pin "C4") (pinfunction "PB03_C4") (pintype "bidirectional"))
    )
    (net (code "127") (name "unconnected-(EDBG-PB04-PadA3)") (class "Default")
      (node (ref "EDBG") (pin "A3") (pinfunction "PB04_A3") (pintype "bidirectional"))
    )
    (net (code "128") (name "unconnected-(EDBG-PB06-PadD7)") (class "Default")
      (node (ref "EDBG") (pin "D7") (pinfunction "PB06_D7") (pintype "bidirectional"))
    )
    (net (code "129") (name "unconnected-(EDBG-PB08-PadC6)") (class "Default")
      (node (ref "EDBG") (pin "C6") (pinfunction "PB08_C6") (pintype "bidirectional"))
    )
    (net (code "130") (name "unconnected-(EDBG-PB10-PadD5)") (class "Default")
      (node (ref "EDBG") (pin "D5") (pinfunction "PB10_D5") (pintype "bidirectional"))
    )
    (net (code "131") (name "unconnected-(EDBG-PB11-PadC1)") (class "Default")
      (node (ref "EDBG") (pin "C1") (pinfunction "PB11_C1") (pintype "bidirectional"))
    )
    (net (code "132") (name "unconnected-(EDBG-PC00{slash}PX14-PadK5)") (class "Default")
      (node (ref "EDBG") (pin "K5") (pinfunction "PC00/PX14_K5") (pintype "bidirectional"))
    )
    (net (code "133") (name "unconnected-(EDBG-PC01-PadK6)") (class "Default")
      (node (ref "EDBG") (pin "K6") (pinfunction "PC01_K6") (pintype "bidirectional"))
    )
    (net (code "134") (name "unconnected-(EDBG-PC04-PadB7)") (class "Default")
      (node (ref "EDBG") (pin "B7") (pinfunction "PC04_B7") (pintype "bidirectional"))
    )
    (net (code "135") (name "unconnected-(EDBG-PC05-PadA7)") (class "Default")
      (node (ref "EDBG") (pin "A7") (pinfunction "PC05_A7") (pintype "bidirectional"))
    )
    (net (code "136") (name "unconnected-(EDBG-PX00-PadG4)") (class "Default")
      (node (ref "EDBG") (pin "G4") (pinfunction "PX00_G4") (pintype "bidirectional"))
    )
    (net (code "137") (name "unconnected-(EDBG-PX01-PadG2)") (class "Default")
      (node (ref "EDBG") (pin "G2") (pinfunction "PX01_G2") (pintype "bidirectional"))
    )
    (net (code "138") (name "unconnected-(EDBG-PX02-PadG3)") (class "Default")
      (node (ref "EDBG") (pin "G3") (pinfunction "PX02_G3") (pintype "bidirectional"))
    )
    (net (code "139") (name "unconnected-(EDBG-PX03-PadJ1)") (class "Default")
      (node (ref "EDBG") (pin "J1") (pinfunction "PX03_J1") (pintype "bidirectional"))
    )
    (net (code "140") (name "unconnected-(EDBG-PX04-PadH1)") (class "Default")
      (node (ref "EDBG") (pin "H1") (pinfunction "PX04_H1") (pintype "bidirectional"))
    )
    (net (code "141") (name "unconnected-(EDBG-PX05-PadG1)") (class "Default")
      (node (ref "EDBG") (pin "G1") (pinfunction "PX05_G1") (pintype "bidirectional"))
    )
    (net (code "142") (name "unconnected-(EDBG-PX06-PadF3)") (class "Default")
      (node (ref "EDBG") (pin "F3") (pinfunction "PX06_F3") (pintype "bidirectional"))
    )
    (net (code "143") (name "unconnected-(EDBG-PX07-PadF4)") (class "Default")
      (node (ref "EDBG") (pin "F4") (pinfunction "PX07_F4") (pintype "bidirectional"))
    )
    (net (code "144") (name "unconnected-(EDBG-PX08-PadE3)") (class "Default")
      (node (ref "EDBG") (pin "E3") (pinfunction "PX08_E3") (pintype "bidirectional"))
    )
    (net (code "145") (name "unconnected-(EDBG-PX09-PadE4)") (class "Default")
      (node (ref "EDBG") (pin "E4") (pinfunction "PX09_E4") (pintype "bidirectional"))
    )
    (net (code "146") (name "unconnected-(EDBG-PX10-PadD2)") (class "Default")
      (node (ref "EDBG") (pin "D2") (pinfunction "PX10_D2") (pintype "bidirectional"))
    )
    (net (code "147") (name "unconnected-(EDBG-PX12-PadD1)") (class "Default")
      (node (ref "EDBG") (pin "D1") (pinfunction "PX12_D1") (pintype "bidirectional"))
    )
    (net (code "148") (name "unconnected-(EDBG-PX13-PadD3)") (class "Default")
      (node (ref "EDBG") (pin "D3") (pinfunction "PX13_D3") (pintype "bidirectional"))
    )
    (net (code "149") (name "unconnected-(EDBG-PX23-PadK1)") (class "Default")
      (node (ref "EDBG") (pin "K1") (pinfunction "PX23_K1") (pintype "bidirectional"))
    )
    (net (code "150") (name "unconnected-(EDBG-PX24-PadJ2)") (class "Default")
      (node (ref "EDBG") (pin "J2") (pinfunction "PX24_J2") (pintype "bidirectional"))
    )
    (net (code "151") (name "unconnected-(EDBG-PX25-PadH4)") (class "Default")
      (node (ref "EDBG") (pin "H4") (pinfunction "PX25_H4") (pintype "bidirectional"))
    )
    (net (code "152") (name "unconnected-(EDBG-PX26-PadJ3)") (class "Default")
      (node (ref "EDBG") (pin "J3") (pinfunction "PX26_J3") (pintype "bidirectional"))
    )
    (net (code "153") (name "unconnected-(EDBG-PX31-PadH5)") (class "Default")
      (node (ref "EDBG") (pin "H5") (pinfunction "PX31_H5") (pintype "bidirectional"))
    )
    (net (code "154") (name "unconnected-(EDBG-PX53{slash}PX16-PadD4)") (class "Default")
      (node (ref "EDBG") (pin "D4") (pinfunction "PX53/PX16_D4") (pintype "bidirectional"))
    )
    (net (code "155") (name "unconnected-(J100-Pad6)") (class "Default")
      (node (ref "J100") (pin "6") (pinfunction "6_6") (pintype "passive"))
    )
    (net (code "156") (name "unconnected-(J100-Pad7)") (class "Default")
      (node (ref "J100") (pin "7") (pinfunction "7_7") (pintype "passive"))
    )
    (net (code "157") (name "unconnected-(J100-Pad8)") (class "Default")
      (node (ref "J100") (pin "8") (pinfunction "8_8") (pintype "passive"))
    )
    (net (code "158") (name "unconnected-(J300-PadID)") (class "Default")
      (node (ref "J300") (pin "ID") (pinfunction "ID_ID") (pintype "bidirectional"))
    )
    (net (code "159") (name "unconnected-(J301-Pad7)") (class "Default")
      (node (ref "J301") (pin "7") (pinfunction "7_7") (pintype "passive"))
    )
    (net (code "160") (name "unconnected-(J301-Pad8)") (class "Default")
      (node (ref "J301") (pin "8") (pinfunction "8_8") (pintype "passive"))
    )
    (net (code "161") (name "unconnected-(X300-GND-Pad2)") (class "Default")
      (node (ref "X300") (pin "2") (pinfunction "GND_2") (pintype "passive"))
    )
    (net (code "162") (name "unconnected-(X300-GND-Pad4)") (class "Default")
      (node (ref "X300") (pin "4") (pinfunction "GND_4") (pintype "passive"))
    )
  )
)
